# LED_Matrix16x16.net
KiCad netlist of a schematic drawn in Altium Designer
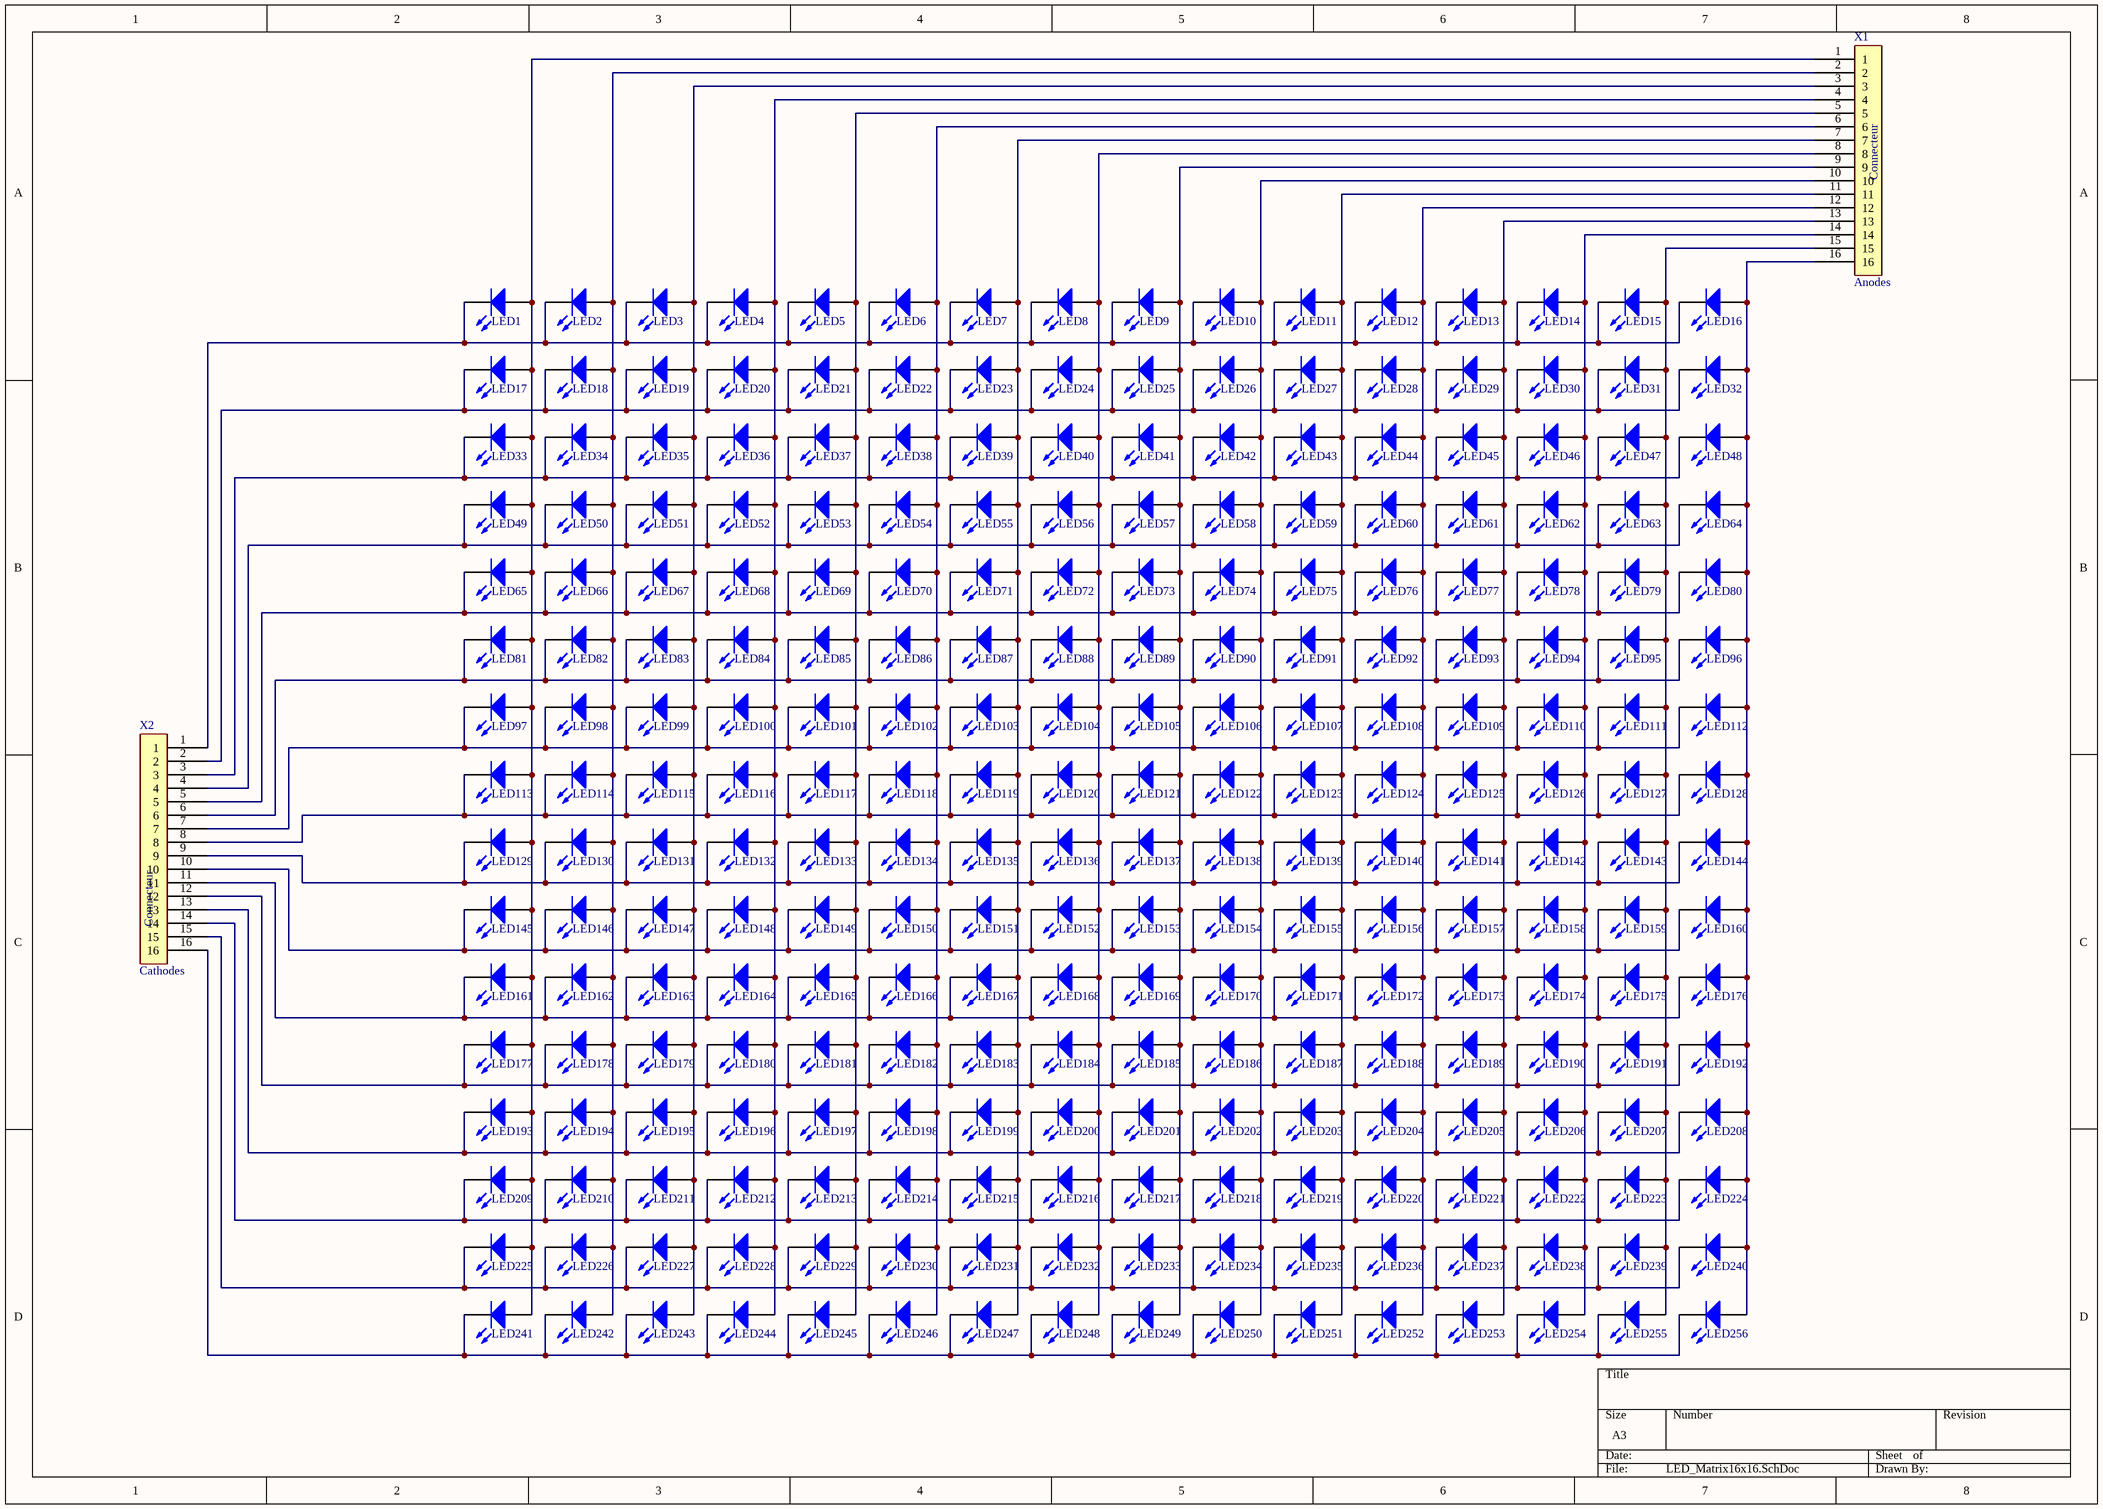
[diagram p0: LED_Matrix16x16.SchDoc]

(export (version "E")
  (design (tool "Eeschema 10.0.6"))
  (components
    (comp (ref "LED1")
      (value "KPT-2012SRC-PRV")
      (footprint "0805_LED")
      (libsource (lib "2008_SablierElectronique_SCHLIB") (part "KPT-2012SRC-PRV"))
    )
    (comp (ref "LED2")
      (value "KPT-2012SRC-PRV")
      (footprint "0805_LED")
      (libsource (lib "2008_SablierElectronique_SCHLIB") (part "KPT-2012SRC-PRV"))
    )
    (comp (ref "LED3")
      (value "KPT-2012SRC-PRV")
      (footprint "0805_LED")
      (libsource (lib "2008_SablierElectronique_SCHLIB") (part "KPT-2012SRC-PRV"))
    )
    (comp (ref "LED4")
      (value "KPT-2012SRC-PRV")
      (footprint "0805_LED")
      (libsource (lib "2008_SablierElectronique_SCHLIB") (part "KPT-2012SRC-PRV"))
    )
    (comp (ref "LED5")
      (value "KPT-2012SRC-PRV")
      (footprint "0805_LED")
      (libsource (lib "2008_SablierElectronique_SCHLIB") (part "KPT-2012SRC-PRV"))
    )
    (comp (ref "LED6")
      (value "KPT-2012SRC-PRV")
      (footprint "0805_LED")
      (libsource (lib "2008_SablierElectronique_SCHLIB") (part "KPT-2012SRC-PRV"))
    )
    (comp (ref "LED7")
      (value "KPT-2012SRC-PRV")
      (footprint "0805_LED")
      (libsource (lib "2008_SablierElectronique_SCHLIB") (part "KPT-2012SRC-PRV"))
    )
    (comp (ref "LED8")
      (value "KPT-2012SRC-PRV")
      (footprint "0805_LED")
      (libsource (lib "2008_SablierElectronique_SCHLIB") (part "KPT-2012SRC-PRV"))
    )
    (comp (ref "LED9")
      (value "KPT-2012SRC-PRV")
      (footprint "0805_LED")
      (libsource (lib "2008_SablierElectronique_SCHLIB") (part "KPT-2012SRC-PRV"))
    )
    (comp (ref "LED10")
      (value "KPT-2012SRC-PRV")
      (footprint "0805_LED")
      (libsource (lib "2008_SablierElectronique_SCHLIB") (part "KPT-2012SRC-PRV"))
    )
    (comp (ref "LED11")
      (value "KPT-2012SRC-PRV")
      (footprint "0805_LED")
      (libsource (lib "2008_SablierElectronique_SCHLIB") (part "KPT-2012SRC-PRV"))
    )
    (comp (ref "LED12")
      (value "KPT-2012SRC-PRV")
      (footprint "0805_LED")
      (libsource (lib "2008_SablierElectronique_SCHLIB") (part "KPT-2012SRC-PRV"))
    )
    (comp (ref "LED13")
      (value "KPT-2012SRC-PRV")
      (footprint "0805_LED")
      (libsource (lib "2008_SablierElectronique_SCHLIB") (part "KPT-2012SRC-PRV"))
    )
    (comp (ref "LED14")
      (value "KPT-2012SRC-PRV")
      (footprint "0805_LED")
      (libsource (lib "2008_SablierElectronique_SCHLIB") (part "KPT-2012SRC-PRV"))
    )
    (comp (ref "LED15")
      (value "KPT-2012SRC-PRV")
      (footprint "0805_LED")
      (libsource (lib "2008_SablierElectronique_SCHLIB") (part "KPT-2012SRC-PRV"))
    )
    (comp (ref "LED16")
      (value "KPT-2012SRC-PRV")
      (footprint "0805_LED")
      (libsource (lib "2008_SablierElectronique_SCHLIB") (part "KPT-2012SRC-PRV"))
    )
    (comp (ref "LED17")
      (value "KPT-2012SRC-PRV")
      (footprint "0805_LED")
      (libsource (lib "2008_SablierElectronique_SCHLIB") (part "KPT-2012SRC-PRV"))
    )
    (comp (ref "LED18")
      (value "KPT-2012SRC-PRV")
      (footprint "0805_LED")
      (libsource (lib "2008_SablierElectronique_SCHLIB") (part "KPT-2012SRC-PRV"))
    )
    (comp (ref "LED19")
      (value "KPT-2012SRC-PRV")
      (footprint "0805_LED")
      (libsource (lib "2008_SablierElectronique_SCHLIB") (part "KPT-2012SRC-PRV"))
    )
    (comp (ref "LED20")
      (value "KPT-2012SRC-PRV")
      (footprint "0805_LED")
      (libsource (lib "2008_SablierElectronique_SCHLIB") (part "KPT-2012SRC-PRV"))
    )
    (comp (ref "LED21")
      (value "KPT-2012SRC-PRV")
      (footprint "0805_LED")
      (libsource (lib "2008_SablierElectronique_SCHLIB") (part "KPT-2012SRC-PRV"))
    )
    (comp (ref "LED22")
      (value "KPT-2012SRC-PRV")
      (footprint "0805_LED")
      (libsource (lib "2008_SablierElectronique_SCHLIB") (part "KPT-2012SRC-PRV"))
    )
    (comp (ref "LED23")
      (value "KPT-2012SRC-PRV")
      (footprint "0805_LED")
      (libsource (lib "2008_SablierElectronique_SCHLIB") (part "KPT-2012SRC-PRV"))
    )
    (comp (ref "LED24")
      (value "KPT-2012SRC-PRV")
      (footprint "0805_LED")
      (libsource (lib "2008_SablierElectronique_SCHLIB") (part "KPT-2012SRC-PRV"))
    )
    (comp (ref "LED25")
      (value "KPT-2012SRC-PRV")
      (footprint "0805_LED")
      (libsource (lib "2008_SablierElectronique_SCHLIB") (part "KPT-2012SRC-PRV"))
    )
    (comp (ref "LED26")
      (value "KPT-2012SRC-PRV")
      (footprint "0805_LED")
      (libsource (lib "2008_SablierElectronique_SCHLIB") (part "KPT-2012SRC-PRV"))
    )
    (comp (ref "LED27")
      (value "KPT-2012SRC-PRV")
      (footprint "0805_LED")
      (libsource (lib "2008_SablierElectronique_SCHLIB") (part "KPT-2012SRC-PRV"))
    )
    (comp (ref "LED28")
      (value "KPT-2012SRC-PRV")
      (footprint "0805_LED")
      (libsource (lib "2008_SablierElectronique_SCHLIB") (part "KPT-2012SRC-PRV"))
    )
    (comp (ref "LED29")
      (value "KPT-2012SRC-PRV")
      (footprint "0805_LED")
      (libsource (lib "2008_SablierElectronique_SCHLIB") (part "KPT-2012SRC-PRV"))
    )
    (comp (ref "LED30")
      (value "KPT-2012SRC-PRV")
      (footprint "0805_LED")
      (libsource (lib "2008_SablierElectronique_SCHLIB") (part "KPT-2012SRC-PRV"))
    )
    (comp (ref "LED31")
      (value "KPT-2012SRC-PRV")
      (footprint "0805_LED")
      (libsource (lib "2008_SablierElectronique_SCHLIB") (part "KPT-2012SRC-PRV"))
    )
    (comp (ref "LED32")
      (value "KPT-2012SRC-PRV")
      (footprint "0805_LED")
      (libsource (lib "2008_SablierElectronique_SCHLIB") (part "KPT-2012SRC-PRV"))
    )
    (comp (ref "LED33")
      (value "KPT-2012SRC-PRV")
      (footprint "0805_LED")
      (libsource (lib "2008_SablierElectronique_SCHLIB") (part "KPT-2012SRC-PRV"))
    )
    (comp (ref "LED34")
      (value "KPT-2012SRC-PRV")
      (footprint "0805_LED")
      (libsource (lib "2008_SablierElectronique_SCHLIB") (part "KPT-2012SRC-PRV"))
    )
    (comp (ref "LED35")
      (value "KPT-2012SRC-PRV")
      (footprint "0805_LED")
      (libsource (lib "2008_SablierElectronique_SCHLIB") (part "KPT-2012SRC-PRV"))
    )
    (comp (ref "LED36")
      (value "KPT-2012SRC-PRV")
      (footprint "0805_LED")
      (libsource (lib "2008_SablierElectronique_SCHLIB") (part "KPT-2012SRC-PRV"))
    )
    (comp (ref "LED37")
      (value "KPT-2012SRC-PRV")
      (footprint "0805_LED")
      (libsource (lib "2008_SablierElectronique_SCHLIB") (part "KPT-2012SRC-PRV"))
    )
    (comp (ref "LED38")
      (value "KPT-2012SRC-PRV")
      (footprint "0805_LED")
      (libsource (lib "2008_SablierElectronique_SCHLIB") (part "KPT-2012SRC-PRV"))
    )
    (comp (ref "LED39")
      (value "KPT-2012SRC-PRV")
      (footprint "0805_LED")
      (libsource (lib "2008_SablierElectronique_SCHLIB") (part "KPT-2012SRC-PRV"))
    )
    (comp (ref "LED40")
      (value "KPT-2012SRC-PRV")
      (footprint "0805_LED")
      (libsource (lib "2008_SablierElectronique_SCHLIB") (part "KPT-2012SRC-PRV"))
    )
    (comp (ref "LED41")
      (value "KPT-2012SRC-PRV")
      (footprint "0805_LED")
      (libsource (lib "2008_SablierElectronique_SCHLIB") (part "KPT-2012SRC-PRV"))
    )
    (comp (ref "LED42")
      (value "KPT-2012SRC-PRV")
      (footprint "0805_LED")
      (libsource (lib "2008_SablierElectronique_SCHLIB") (part "KPT-2012SRC-PRV"))
    )
    (comp (ref "LED43")
      (value "KPT-2012SRC-PRV")
      (footprint "0805_LED")
      (libsource (lib "2008_SablierElectronique_SCHLIB") (part "KPT-2012SRC-PRV"))
    )
    (comp (ref "LED44")
      (value "KPT-2012SRC-PRV")
      (footprint "0805_LED")
      (libsource (lib "2008_SablierElectronique_SCHLIB") (part "KPT-2012SRC-PRV"))
    )
    (comp (ref "LED45")
      (value "KPT-2012SRC-PRV")
      (footprint "0805_LED")
      (libsource (lib "2008_SablierElectronique_SCHLIB") (part "KPT-2012SRC-PRV"))
    )
    (comp (ref "LED46")
      (value "KPT-2012SRC-PRV")
      (footprint "0805_LED")
      (libsource (lib "2008_SablierElectronique_SCHLIB") (part "KPT-2012SRC-PRV"))
    )
    (comp (ref "LED47")
      (value "KPT-2012SRC-PRV")
      (footprint "0805_LED")
      (libsource (lib "2008_SablierElectronique_SCHLIB") (part "KPT-2012SRC-PRV"))
    )
    (comp (ref "LED48")
      (value "KPT-2012SRC-PRV")
      (footprint "0805_LED")
      (libsource (lib "2008_SablierElectronique_SCHLIB") (part "KPT-2012SRC-PRV"))
    )
    (comp (ref "LED49")
      (value "KPT-2012SRC-PRV")
      (footprint "0805_LED")
      (libsource (lib "2008_SablierElectronique_SCHLIB") (part "KPT-2012SRC-PRV"))
    )
    (comp (ref "LED50")
      (value "KPT-2012SRC-PRV")
      (footprint "0805_LED")
      (libsource (lib "2008_SablierElectronique_SCHLIB") (part "KPT-2012SRC-PRV"))
    )
    (comp (ref "LED51")
      (value "KPT-2012SRC-PRV")
      (footprint "0805_LED")
      (libsource (lib "2008_SablierElectronique_SCHLIB") (part "KPT-2012SRC-PRV"))
    )
    (comp (ref "LED52")
      (value "KPT-2012SRC-PRV")
      (footprint "0805_LED")
      (libsource (lib "2008_SablierElectronique_SCHLIB") (part "KPT-2012SRC-PRV"))
    )
    (comp (ref "LED53")
      (value "KPT-2012SRC-PRV")
      (footprint "0805_LED")
      (libsource (lib "2008_SablierElectronique_SCHLIB") (part "KPT-2012SRC-PRV"))
    )
    (comp (ref "LED54")
      (value "KPT-2012SRC-PRV")
      (footprint "0805_LED")
      (libsource (lib "2008_SablierElectronique_SCHLIB") (part "KPT-2012SRC-PRV"))
    )
    (comp (ref "LED55")
      (value "KPT-2012SRC-PRV")
      (footprint "0805_LED")
      (libsource (lib "2008_SablierElectronique_SCHLIB") (part "KPT-2012SRC-PRV"))
    )
    (comp (ref "LED56")
      (value "KPT-2012SRC-PRV")
      (footprint "0805_LED")
      (libsource (lib "2008_SablierElectronique_SCHLIB") (part "KPT-2012SRC-PRV"))
    )
    (comp (ref "LED57")
      (value "KPT-2012SRC-PRV")
      (footprint "0805_LED")
      (libsource (lib "2008_SablierElectronique_SCHLIB") (part "KPT-2012SRC-PRV"))
    )
    (comp (ref "LED58")
      (value "KPT-2012SRC-PRV")
      (footprint "0805_LED")
      (libsource (lib "2008_SablierElectronique_SCHLIB") (part "KPT-2012SRC-PRV"))
    )
    (comp (ref "LED59")
      (value "KPT-2012SRC-PRV")
      (footprint "0805_LED")
      (libsource (lib "2008_SablierElectronique_SCHLIB") (part "KPT-2012SRC-PRV"))
    )
    (comp (ref "LED60")
      (value "KPT-2012SRC-PRV")
      (footprint "0805_LED")
      (libsource (lib "2008_SablierElectronique_SCHLIB") (part "KPT-2012SRC-PRV"))
    )
    (comp (ref "LED61")
      (value "KPT-2012SRC-PRV")
      (footprint "0805_LED")
      (libsource (lib "2008_SablierElectronique_SCHLIB") (part "KPT-2012SRC-PRV"))
    )
    (comp (ref "LED62")
      (value "KPT-2012SRC-PRV")
      (footprint "0805_LED")
      (libsource (lib "2008_SablierElectronique_SCHLIB") (part "KPT-2012SRC-PRV"))
    )
    (comp (ref "LED63")
      (value "KPT-2012SRC-PRV")
      (footprint "0805_LED")
      (libsource (lib "2008_SablierElectronique_SCHLIB") (part "KPT-2012SRC-PRV"))
    )
    (comp (ref "LED64")
      (value "KPT-2012SRC-PRV")
      (footprint "0805_LED")
      (libsource (lib "2008_SablierElectronique_SCHLIB") (part "KPT-2012SRC-PRV"))
    )
    (comp (ref "LED65")
      (value "KPT-2012SRC-PRV")
      (footprint "0805_LED")
      (libsource (lib "2008_SablierElectronique_SCHLIB") (part "KPT-2012SRC-PRV"))
    )
    (comp (ref "LED66")
      (value "KPT-2012SRC-PRV")
      (footprint "0805_LED")
      (libsource (lib "2008_SablierElectronique_SCHLIB") (part "KPT-2012SRC-PRV"))
    )
    (comp (ref "LED67")
      (value "KPT-2012SRC-PRV")
      (footprint "0805_LED")
      (libsource (lib "2008_SablierElectronique_SCHLIB") (part "KPT-2012SRC-PRV"))
    )
    (comp (ref "LED68")
      (value "KPT-2012SRC-PRV")
      (footprint "0805_LED")
      (libsource (lib "2008_SablierElectronique_SCHLIB") (part "KPT-2012SRC-PRV"))
    )
    (comp (ref "LED69")
      (value "KPT-2012SRC-PRV")
      (footprint "0805_LED")
      (libsource (lib "2008_SablierElectronique_SCHLIB") (part "KPT-2012SRC-PRV"))
    )
    (comp (ref "LED70")
      (value "KPT-2012SRC-PRV")
      (footprint "0805_LED")
      (libsource (lib "2008_SablierElectronique_SCHLIB") (part "KPT-2012SRC-PRV"))
    )
    (comp (ref "LED71")
      (value "KPT-2012SRC-PRV")
      (footprint "0805_LED")
      (libsource (lib "2008_SablierElectronique_SCHLIB") (part "KPT-2012SRC-PRV"))
    )
    (comp (ref "LED72")
      (value "KPT-2012SRC-PRV")
      (footprint "0805_LED")
      (libsource (lib "2008_SablierElectronique_SCHLIB") (part "KPT-2012SRC-PRV"))
    )
    (comp (ref "LED73")
      (value "KPT-2012SRC-PRV")
      (footprint "0805_LED")
      (libsource (lib "2008_SablierElectronique_SCHLIB") (part "KPT-2012SRC-PRV"))
    )
    (comp (ref "LED74")
      (value "KPT-2012SRC-PRV")
      (footprint "0805_LED")
      (libsource (lib "2008_SablierElectronique_SCHLIB") (part "KPT-2012SRC-PRV"))
    )
    (comp (ref "LED75")
      (value "KPT-2012SRC-PRV")
      (footprint "0805_LED")
      (libsource (lib "2008_SablierElectronique_SCHLIB") (part "KPT-2012SRC-PRV"))
    )
    (comp (ref "LED76")
      (value "KPT-2012SRC-PRV")
      (footprint "0805_LED")
      (libsource (lib "2008_SablierElectronique_SCHLIB") (part "KPT-2012SRC-PRV"))
    )
    (comp (ref "LED77")
      (value "KPT-2012SRC-PRV")
      (footprint "0805_LED")
      (libsource (lib "2008_SablierElectronique_SCHLIB") (part "KPT-2012SRC-PRV"))
    )
    (comp (ref "LED78")
      (value "KPT-2012SRC-PRV")
      (footprint "0805_LED")
      (libsource (lib "2008_SablierElectronique_SCHLIB") (part "KPT-2012SRC-PRV"))
    )
    (comp (ref "LED79")
      (value "KPT-2012SRC-PRV")
      (footprint "0805_LED")
      (libsource (lib "2008_SablierElectronique_SCHLIB") (part "KPT-2012SRC-PRV"))
    )
    (comp (ref "LED80")
      (value "KPT-2012SRC-PRV")
      (footprint "0805_LED")
      (libsource (lib "2008_SablierElectronique_SCHLIB") (part "KPT-2012SRC-PRV"))
    )
    (comp (ref "LED81")
      (value "KPT-2012SRC-PRV")
      (footprint "0805_LED")
      (libsource (lib "2008_SablierElectronique_SCHLIB") (part "KPT-2012SRC-PRV"))
    )
    (comp (ref "LED82")
      (value "KPT-2012SRC-PRV")
      (footprint "0805_LED")
      (libsource (lib "2008_SablierElectronique_SCHLIB") (part "KPT-2012SRC-PRV"))
    )
    (comp (ref "LED83")
      (value "KPT-2012SRC-PRV")
      (footprint "0805_LED")
      (libsource (lib "2008_SablierElectronique_SCHLIB") (part "KPT-2012SRC-PRV"))
    )
    (comp (ref "LED84")
      (value "KPT-2012SRC-PRV")
      (footprint "0805_LED")
      (libsource (lib "2008_SablierElectronique_SCHLIB") (part "KPT-2012SRC-PRV"))
    )
    (comp (ref "LED85")
      (value "KPT-2012SRC-PRV")
      (footprint "0805_LED")
      (libsource (lib "2008_SablierElectronique_SCHLIB") (part "KPT-2012SRC-PRV"))
    )
    (comp (ref "LED86")
      (value "KPT-2012SRC-PRV")
      (footprint "0805_LED")
      (libsource (lib "2008_SablierElectronique_SCHLIB") (part "KPT-2012SRC-PRV"))
    )
    (comp (ref "LED87")
      (value "KPT-2012SRC-PRV")
      (footprint "0805_LED")
      (libsource (lib "2008_SablierElectronique_SCHLIB") (part "KPT-2012SRC-PRV"))
    )
    (comp (ref "LED88")
      (value "KPT-2012SRC-PRV")
      (footprint "0805_LED")
      (libsource (lib "2008_SablierElectronique_SCHLIB") (part "KPT-2012SRC-PRV"))
    )
    (comp (ref "LED89")
      (value "KPT-2012SRC-PRV")
      (footprint "0805_LED")
      (libsource (lib "2008_SablierElectronique_SCHLIB") (part "KPT-2012SRC-PRV"))
    )
    (comp (ref "LED90")
      (value "KPT-2012SRC-PRV")
      (footprint "0805_LED")
      (libsource (lib "2008_SablierElectronique_SCHLIB") (part "KPT-2012SRC-PRV"))
    )
    (comp (ref "LED91")
      (value "KPT-2012SRC-PRV")
      (footprint "0805_LED")
      (libsource (lib "2008_SablierElectronique_SCHLIB") (part "KPT-2012SRC-PRV"))
    )
    (comp (ref "LED92")
      (value "KPT-2012SRC-PRV")
      (footprint "0805_LED")
      (libsource (lib "2008_SablierElectronique_SCHLIB") (part "KPT-2012SRC-PRV"))
    )
    (comp (ref "LED93")
      (value "KPT-2012SRC-PRV")
      (footprint "0805_LED")
      (libsource (lib "2008_SablierElectronique_SCHLIB") (part "KPT-2012SRC-PRV"))
    )
    (comp (ref "LED94")
      (value "KPT-2012SRC-PRV")
      (footprint "0805_LED")
      (libsource (lib "2008_SablierElectronique_SCHLIB") (part "KPT-2012SRC-PRV"))
    )
    (comp (ref "LED95")
      (value "KPT-2012SRC-PRV")
      (footprint "0805_LED")
      (libsource (lib "2008_SablierElectronique_SCHLIB") (part "KPT-2012SRC-PRV"))
    )
    (comp (ref "LED96")
      (value "KPT-2012SRC-PRV")
      (footprint "0805_LED")
      (libsource (lib "2008_SablierElectronique_SCHLIB") (part "KPT-2012SRC-PRV"))
    )
    (comp (ref "LED97")
      (value "KPT-2012SRC-PRV")
      (footprint "0805_LED")
      (libsource (lib "2008_SablierElectronique_SCHLIB") (part "KPT-2012SRC-PRV"))
    )
    (comp (ref "LED98")
      (value "KPT-2012SRC-PRV")
      (footprint "0805_LED")
      (libsource (lib "2008_SablierElectronique_SCHLIB") (part "KPT-2012SRC-PRV"))
    )
    (comp (ref "LED99")
      (value "KPT-2012SRC-PRV")
      (footprint "0805_LED")
      (libsource (lib "2008_SablierElectronique_SCHLIB") (part "KPT-2012SRC-PRV"))
    )
    (comp (ref "LED100")
      (value "KPT-2012SRC-PRV")
      (footprint "0805_LED")
      (libsource (lib "2008_SablierElectronique_SCHLIB") (part "KPT-2012SRC-PRV"))
    )
    (comp (ref "LED101")
      (value "KPT-2012SRC-PRV")
      (footprint "0805_LED")
      (libsource (lib "2008_SablierElectronique_SCHLIB") (part "KPT-2012SRC-PRV"))
    )
    (comp (ref "LED102")
      (value "KPT-2012SRC-PRV")
      (footprint "0805_LED")
      (libsource (lib "2008_SablierElectronique_SCHLIB") (part "KPT-2012SRC-PRV"))
    )
    (comp (ref "LED103")
      (value "KPT-2012SRC-PRV")
      (footprint "0805_LED")
      (libsource (lib "2008_SablierElectronique_SCHLIB") (part "KPT-2012SRC-PRV"))
    )
    (comp (ref "LED104")
      (value "KPT-2012SRC-PRV")
      (footprint "0805_LED")
      (libsource (lib "2008_SablierElectronique_SCHLIB") (part "KPT-2012SRC-PRV"))
    )
    (comp (ref "LED105")
      (value "KPT-2012SRC-PRV")
      (footprint "0805_LED")
      (libsource (lib "2008_SablierElectronique_SCHLIB") (part "KPT-2012SRC-PRV"))
    )
    (comp (ref "LED106")
      (value "KPT-2012SRC-PRV")
      (footprint "0805_LED")
      (libsource (lib "2008_SablierElectronique_SCHLIB") (part "KPT-2012SRC-PRV"))
    )
    (comp (ref "LED107")
      (value "KPT-2012SRC-PRV")
      (footprint "0805_LED")
      (libsource (lib "2008_SablierElectronique_SCHLIB") (part "KPT-2012SRC-PRV"))
    )
    (comp (ref "LED108")
      (value "KPT-2012SRC-PRV")
      (footprint "0805_LED")
      (libsource (lib "2008_SablierElectronique_SCHLIB") (part "KPT-2012SRC-PRV"))
    )
    (comp (ref "LED109")
      (value "KPT-2012SRC-PRV")
      (footprint "0805_LED")
      (libsource (lib "2008_SablierElectronique_SCHLIB") (part "KPT-2012SRC-PRV"))
    )
    (comp (ref "LED110")
      (value "KPT-2012SRC-PRV")
      (footprint "0805_LED")
      (libsource (lib "2008_SablierElectronique_SCHLIB") (part "KPT-2012SRC-PRV"))
    )
    (comp (ref "LED111")
      (value "KPT-2012SRC-PRV")
      (footprint "0805_LED")
      (libsource (lib "2008_SablierElectronique_SCHLIB") (part "KPT-2012SRC-PRV"))
    )
    (comp (ref "LED112")
      (value "KPT-2012SRC-PRV")
      (footprint "0805_LED")
      (libsource (lib "2008_SablierElectronique_SCHLIB") (part "KPT-2012SRC-PRV"))
    )
    (comp (ref "LED113")
      (value "KPT-2012SRC-PRV")
      (footprint "0805_LED")
      (libsource (lib "2008_SablierElectronique_SCHLIB") (part "KPT-2012SRC-PRV"))
    )
    (comp (ref "LED114")
      (value "KPT-2012SRC-PRV")
      (footprint "0805_LED")
      (libsource (lib "2008_SablierElectronique_SCHLIB") (part "KPT-2012SRC-PRV"))
    )
    (comp (ref "LED115")
      (value "KPT-2012SRC-PRV")
      (footprint "0805_LED")
      (libsource (lib "2008_SablierElectronique_SCHLIB") (part "KPT-2012SRC-PRV"))
    )
    (comp (ref "LED116")
      (value "KPT-2012SRC-PRV")
      (footprint "0805_LED")
      (libsource (lib "2008_SablierElectronique_SCHLIB") (part "KPT-2012SRC-PRV"))
    )
    (comp (ref "LED117")
      (value "KPT-2012SRC-PRV")
      (footprint "0805_LED")
      (libsource (lib "2008_SablierElectronique_SCHLIB") (part "KPT-2012SRC-PRV"))
    )
    (comp (ref "LED118")
      (value "KPT-2012SRC-PRV")
      (footprint "0805_LED")
      (libsource (lib "2008_SablierElectronique_SCHLIB") (part "KPT-2012SRC-PRV"))
    )
    (comp (ref "LED119")
      (value "KPT-2012SRC-PRV")
      (footprint "0805_LED")
      (libsource (lib "2008_SablierElectronique_SCHLIB") (part "KPT-2012SRC-PRV"))
    )
    (comp (ref "LED120")
      (value "KPT-2012SRC-PRV")
      (footprint "0805_LED")
      (libsource (lib "2008_SablierElectronique_SCHLIB") (part "KPT-2012SRC-PRV"))
    )
    (comp (ref "LED121")
      (value "KPT-2012SRC-PRV")
      (footprint "0805_LED")
      (libsource (lib "2008_SablierElectronique_SCHLIB") (part "KPT-2012SRC-PRV"))
    )
    (comp (ref "LED122")
      (value "KPT-2012SRC-PRV")
      (footprint "0805_LED")
      (libsource (lib "2008_SablierElectronique_SCHLIB") (part "KPT-2012SRC-PRV"))
    )
    (comp (ref "LED123")
      (value "KPT-2012SRC-PRV")
      (footprint "0805_LED")
      (libsource (lib "2008_SablierElectronique_SCHLIB") (part "KPT-2012SRC-PRV"))
    )
    (comp (ref "LED124")
      (value "KPT-2012SRC-PRV")
      (footprint "0805_LED")
      (libsource (lib "2008_SablierElectronique_SCHLIB") (part "KPT-2012SRC-PRV"))
    )
    (comp (ref "LED125")
      (value "KPT-2012SRC-PRV")
      (footprint "0805_LED")
      (libsource (lib "2008_SablierElectronique_SCHLIB") (part "KPT-2012SRC-PRV"))
    )
    (comp (ref "LED126")
      (value "KPT-2012SRC-PRV")
      (footprint "0805_LED")
      (libsource (lib "2008_SablierElectronique_SCHLIB") (part "KPT-2012SRC-PRV"))
    )
    (comp (ref "LED127")
      (value "KPT-2012SRC-PRV")
      (footprint "0805_LED")
      (libsource (lib "2008_SablierElectronique_SCHLIB") (part "KPT-2012SRC-PRV"))
    )
    (comp (ref "LED128")
      (value "KPT-2012SRC-PRV")
      (footprint "0805_LED")
      (libsource (lib "2008_SablierElectronique_SCHLIB") (part "KPT-2012SRC-PRV"))
    )
    (comp (ref "LED129")
      (value "KPT-2012SRC-PRV")
      (footprint "0805_LED")
      (libsource (lib "2008_SablierElectronique_SCHLIB") (part "KPT-2012SRC-PRV"))
    )
    (comp (ref "LED130")
      (value "KPT-2012SRC-PRV")
      (footprint "0805_LED")
      (libsource (lib "2008_SablierElectronique_SCHLIB") (part "KPT-2012SRC-PRV"))
    )
    (comp (ref "LED131")
      (value "KPT-2012SRC-PRV")
      (footprint "0805_LED")
      (libsource (lib "2008_SablierElectronique_SCHLIB") (part "KPT-2012SRC-PRV"))
    )
    (comp (ref "LED132")
      (value "KPT-2012SRC-PRV")
      (footprint "0805_LED")
      (libsource (lib "2008_SablierElectronique_SCHLIB") (part "KPT-2012SRC-PRV"))
    )
    (comp (ref "LED133")
      (value "KPT-2012SRC-PRV")
      (footprint "0805_LED")
      (libsource (lib "2008_SablierElectronique_SCHLIB") (part "KPT-2012SRC-PRV"))
    )
    (comp (ref "LED134")
      (value "KPT-2012SRC-PRV")
      (footprint "0805_LED")
      (libsource (lib "2008_SablierElectronique_SCHLIB") (part "KPT-2012SRC-PRV"))
    )
    (comp (ref "LED135")
      (value "KPT-2012SRC-PRV")
      (footprint "0805_LED")
      (libsource (lib "2008_SablierElectronique_SCHLIB") (part "KPT-2012SRC-PRV"))
    )
    (comp (ref "LED136")
      (value "KPT-2012SRC-PRV")
      (footprint "0805_LED")
      (libsource (lib "2008_SablierElectronique_SCHLIB") (part "KPT-2012SRC-PRV"))
    )
    (comp (ref "LED137")
      (value "KPT-2012SRC-PRV")
      (footprint "0805_LED")
      (libsource (lib "2008_SablierElectronique_SCHLIB") (part "KPT-2012SRC-PRV"))
    )
    (comp (ref "LED138")
      (value "KPT-2012SRC-PRV")
      (footprint "0805_LED")
      (libsource (lib "2008_SablierElectronique_SCHLIB") (part "KPT-2012SRC-PRV"))
    )
    (comp (ref "LED139")
      (value "KPT-2012SRC-PRV")
      (footprint "0805_LED")
      (libsource (lib "2008_SablierElectronique_SCHLIB") (part "KPT-2012SRC-PRV"))
    )
    (comp (ref "LED140")
      (value "KPT-2012SRC-PRV")
      (footprint "0805_LED")
      (libsource (lib "2008_SablierElectronique_SCHLIB") (part "KPT-2012SRC-PRV"))
    )
    (comp (ref "LED141")
      (value "KPT-2012SRC-PRV")
      (footprint "0805_LED")
      (libsource (lib "2008_SablierElectronique_SCHLIB") (part "KPT-2012SRC-PRV"))
    )
    (comp (ref "LED142")
      (value "KPT-2012SRC-PRV")
      (footprint "0805_LED")
      (libsource (lib "2008_SablierElectronique_SCHLIB") (part "KPT-2012SRC-PRV"))
    )
    (comp (ref "LED143")
      (value "KPT-2012SRC-PRV")
      (footprint "0805_LED")
      (libsource (lib "2008_SablierElectronique_SCHLIB") (part "KPT-2012SRC-PRV"))
    )
    (comp (ref "LED144")
      (value "KPT-2012SRC-PRV")
      (footprint "0805_LED")
      (libsource (lib "2008_SablierElectronique_SCHLIB") (part "KPT-2012SRC-PRV"))
    )
    (comp (ref "LED145")
      (value "KPT-2012SRC-PRV")
      (footprint "0805_LED")
      (libsource (lib "2008_SablierElectronique_SCHLIB") (part "KPT-2012SRC-PRV"))
    )
    (comp (ref "LED146")
      (value "KPT-2012SRC-PRV")
      (footprint "0805_LED")
      (libsource (lib "2008_SablierElectronique_SCHLIB") (part "KPT-2012SRC-PRV"))
    )
    (comp (ref "LED147")
      (value "KPT-2012SRC-PRV")
      (footprint "0805_LED")
      (libsource (lib "2008_SablierElectronique_SCHLIB") (part "KPT-2012SRC-PRV"))
    )
    (comp (ref "LED148")
      (value "KPT-2012SRC-PRV")
      (footprint "0805_LED")
      (libsource (lib "2008_SablierElectronique_SCHLIB") (part "KPT-2012SRC-PRV"))
    )
    (comp (ref "LED149")
      (value "KPT-2012SRC-PRV")
      (footprint "0805_LED")
      (libsource (lib "2008_SablierElectronique_SCHLIB") (part "KPT-2012SRC-PRV"))
    )
    (comp (ref "LED150")
      (value "KPT-2012SRC-PRV")
      (footprint "0805_LED")
      (libsource (lib "2008_SablierElectronique_SCHLIB") (part "KPT-2012SRC-PRV"))
    )
    (comp (ref "LED151")
      (value "KPT-2012SRC-PRV")
      (footprint "0805_LED")
      (libsource (lib "2008_SablierElectronique_SCHLIB") (part "KPT-2012SRC-PRV"))
    )
    (comp (ref "LED152")
      (value "KPT-2012SRC-PRV")
      (footprint "0805_LED")
      (libsource (lib "2008_SablierElectronique_SCHLIB") (part "KPT-2012SRC-PRV"))
    )
    (comp (ref "LED153")
      (value "KPT-2012SRC-PRV")
      (footprint "0805_LED")
      (libsource (lib "2008_SablierElectronique_SCHLIB") (part "KPT-2012SRC-PRV"))
    )
    (comp (ref "LED154")
      (value "KPT-2012SRC-PRV")
      (footprint "0805_LED")
      (libsource (lib "2008_SablierElectronique_SCHLIB") (part "KPT-2012SRC-PRV"))
    )
    (comp (ref "LED155")
      (value "KPT-2012SRC-PRV")
      (footprint "0805_LED")
      (libsource (lib "2008_SablierElectronique_SCHLIB") (part "KPT-2012SRC-PRV"))
    )
    (comp (ref "LED156")
      (value "KPT-2012SRC-PRV")
      (footprint "0805_LED")
      (libsource (lib "2008_SablierElectronique_SCHLIB") (part "KPT-2012SRC-PRV"))
    )
    (comp (ref "LED157")
      (value "KPT-2012SRC-PRV")
      (footprint "0805_LED")
      (libsource (lib "2008_SablierElectronique_SCHLIB") (part "KPT-2012SRC-PRV"))
    )
    (comp (ref "LED158")
      (value "KPT-2012SRC-PRV")
      (footprint "0805_LED")
      (libsource (lib "2008_SablierElectronique_SCHLIB") (part "KPT-2012SRC-PRV"))
    )
    (comp (ref "LED159")
      (value "KPT-2012SRC-PRV")
      (footprint "0805_LED")
      (libsource (lib "2008_SablierElectronique_SCHLIB") (part "KPT-2012SRC-PRV"))
    )
    (comp (ref "LED160")
      (value "KPT-2012SRC-PRV")
      (footprint "0805_LED")
      (libsource (lib "2008_SablierElectronique_SCHLIB") (part "KPT-2012SRC-PRV"))
    )
    (comp (ref "LED161")
      (value "KPT-2012SRC-PRV")
      (footprint "0805_LED")
      (libsource (lib "2008_SablierElectronique_SCHLIB") (part "KPT-2012SRC-PRV"))
    )
    (comp (ref "LED162")
      (value "KPT-2012SRC-PRV")
      (footprint "0805_LED")
      (libsource (lib "2008_SablierElectronique_SCHLIB") (part "KPT-2012SRC-PRV"))
    )
    (comp (ref "LED163")
      (value "KPT-2012SRC-PRV")
      (footprint "0805_LED")
      (libsource (lib "2008_SablierElectronique_SCHLIB") (part "KPT-2012SRC-PRV"))
    )
    (comp (ref "LED164")
      (value "KPT-2012SRC-PRV")
      (footprint "0805_LED")
      (libsource (lib "2008_SablierElectronique_SCHLIB") (part "KPT-2012SRC-PRV"))
    )
    (comp (ref "LED165")
      (value "KPT-2012SRC-PRV")
      (footprint "0805_LED")
      (libsource (lib "2008_SablierElectronique_SCHLIB") (part "KPT-2012SRC-PRV"))
    )
    (comp (ref "LED166")
      (value "KPT-2012SRC-PRV")
      (footprint "0805_LED")
      (libsource (lib "2008_SablierElectronique_SCHLIB") (part "KPT-2012SRC-PRV"))
    )
    (comp (ref "LED167")
      (value "KPT-2012SRC-PRV")
      (footprint "0805_LED")
      (libsource (lib "2008_SablierElectronique_SCHLIB") (part "KPT-2012SRC-PRV"))
    )
    (comp (ref "LED168")
      (value "KPT-2012SRC-PRV")
      (footprint "0805_LED")
      (libsource (lib "2008_SablierElectronique_SCHLIB") (part "KPT-2012SRC-PRV"))
    )
    (comp (ref "LED169")
      (value "KPT-2012SRC-PRV")
      (footprint "0805_LED")
      (libsource (lib "2008_SablierElectronique_SCHLIB") (part "KPT-2012SRC-PRV"))
    )
    (comp (ref "LED170")
      (value "KPT-2012SRC-PRV")
      (footprint "0805_LED")
      (libsource (lib "2008_SablierElectronique_SCHLIB") (part "KPT-2012SRC-PRV"))
    )
    (comp (ref "LED171")
      (value "KPT-2012SRC-PRV")
      (footprint "0805_LED")
      (libsource (lib "2008_SablierElectronique_SCHLIB") (part "KPT-2012SRC-PRV"))
    )
    (comp (ref "LED172")
      (value "KPT-2012SRC-PRV")
      (footprint "0805_LED")
      (libsource (lib "2008_SablierElectronique_SCHLIB") (part "KPT-2012SRC-PRV"))
    )
    (comp (ref "LED173")
      (value "KPT-2012SRC-PRV")
      (footprint "0805_LED")
      (libsource (lib "2008_SablierElectronique_SCHLIB") (part "KPT-2012SRC-PRV"))
    )
    (comp (ref "LED174")
      (value "KPT-2012SRC-PRV")
      (footprint "0805_LED")
      (libsource (lib "2008_SablierElectronique_SCHLIB") (part "KPT-2012SRC-PRV"))
    )
    (comp (ref "LED175")
      (value "KPT-2012SRC-PRV")
      (footprint "0805_LED")
      (libsource (lib "2008_SablierElectronique_SCHLIB") (part "KPT-2012SRC-PRV"))
    )
    (comp (ref "LED176")
      (value "KPT-2012SRC-PRV")
      (footprint "0805_LED")
      (libsource (lib "2008_SablierElectronique_SCHLIB") (part "KPT-2012SRC-PRV"))
    )
    (comp (ref "LED177")
      (value "KPT-2012SRC-PRV")
      (footprint "0805_LED")
      (libsource (lib "2008_SablierElectronique_SCHLIB") (part "KPT-2012SRC-PRV"))
    )
    (comp (ref "LED178")
      (value "KPT-2012SRC-PRV")
      (footprint "0805_LED")
      (libsource (lib "2008_SablierElectronique_SCHLIB") (part "KPT-2012SRC-PRV"))
    )
    (comp (ref "LED179")
      (value "KPT-2012SRC-PRV")
      (footprint "0805_LED")
      (libsource (lib "2008_SablierElectronique_SCHLIB") (part "KPT-2012SRC-PRV"))
    )
    (comp (ref "LED180")
      (value "KPT-2012SRC-PRV")
      (footprint "0805_LED")
      (libsource (lib "2008_SablierElectronique_SCHLIB") (part "KPT-2012SRC-PRV"))
    )
    (comp (ref "LED181")
      (value "KPT-2012SRC-PRV")
      (footprint "0805_LED")
      (libsource (lib "2008_SablierElectronique_SCHLIB") (part "KPT-2012SRC-PRV"))
    )
    (comp (ref "LED182")
      (value "KPT-2012SRC-PRV")
      (footprint "0805_LED")
      (libsource (lib "2008_SablierElectronique_SCHLIB") (part "KPT-2012SRC-PRV"))
    )
    (comp (ref "LED183")
      (value "KPT-2012SRC-PRV")
      (footprint "0805_LED")
      (libsource (lib "2008_SablierElectronique_SCHLIB") (part "KPT-2012SRC-PRV"))
    )
    (comp (ref "LED184")
      (value "KPT-2012SRC-PRV")
      (footprint "0805_LED")
      (libsource (lib "2008_SablierElectronique_SCHLIB") (part "KPT-2012SRC-PRV"))
    )
    (comp (ref "LED185")
      (value "KPT-2012SRC-PRV")
      (footprint "0805_LED")
      (libsource (lib "2008_SablierElectronique_SCHLIB") (part "KPT-2012SRC-PRV"))
    )
    (comp (ref "LED186")
      (value "KPT-2012SRC-PRV")
      (footprint "0805_LED")
      (libsource (lib "2008_SablierElectronique_SCHLIB") (part "KPT-2012SRC-PRV"))
    )
    (comp (ref "LED187")
      (value "KPT-2012SRC-PRV")
      (footprint "0805_LED")
      (libsource (lib "2008_SablierElectronique_SCHLIB") (part "KPT-2012SRC-PRV"))
    )
    (comp (ref "LED188")
      (value "KPT-2012SRC-PRV")
      (footprint "0805_LED")
      (libsource (lib "2008_SablierElectronique_SCHLIB") (part "KPT-2012SRC-PRV"))
    )
    (comp (ref "LED189")
      (value "KPT-2012SRC-PRV")
      (footprint "0805_LED")
      (libsource (lib "2008_SablierElectronique_SCHLIB") (part "KPT-2012SRC-PRV"))
    )
    (comp (ref "LED190")
      (value "KPT-2012SRC-PRV")
      (footprint "0805_LED")
      (libsource (lib "2008_SablierElectronique_SCHLIB") (part "KPT-2012SRC-PRV"))
    )
    (comp (ref "LED191")
      (value "KPT-2012SRC-PRV")
      (footprint "0805_LED")
      (libsource (lib "2008_SablierElectronique_SCHLIB") (part "KPT-2012SRC-PRV"))
    )
    (comp (ref "LED192")
      (value "KPT-2012SRC-PRV")
      (footprint "0805_LED")
      (libsource (lib "2008_SablierElectronique_SCHLIB") (part "KPT-2012SRC-PRV"))
    )
    (comp (ref "LED193")
      (value "KPT-2012SRC-PRV")
      (footprint "0805_LED")
      (libsource (lib "2008_SablierElectronique_SCHLIB") (part "KPT-2012SRC-PRV"))
    )
    (comp (ref "LED194")
      (value "KPT-2012SRC-PRV")
      (footprint "0805_LED")
      (libsource (lib "2008_SablierElectronique_SCHLIB") (part "KPT-2012SRC-PRV"))
    )
    (comp (ref "LED195")
      (value "KPT-2012SRC-PRV")
      (footprint "0805_LED")
      (libsource (lib "2008_SablierElectronique_SCHLIB") (part "KPT-2012SRC-PRV"))
    )
    (comp (ref "LED196")
      (value "KPT-2012SRC-PRV")
      (footprint "0805_LED")
      (libsource (lib "2008_SablierElectronique_SCHLIB") (part "KPT-2012SRC-PRV"))
    )
    (comp (ref "LED197")
      (value "KPT-2012SRC-PRV")
      (footprint "0805_LED")
      (libsource (lib "2008_SablierElectronique_SCHLIB") (part "KPT-2012SRC-PRV"))
    )
    (comp (ref "LED198")
      (value "KPT-2012SRC-PRV")
      (footprint "0805_LED")
      (libsource (lib "2008_SablierElectronique_SCHLIB") (part "KPT-2012SRC-PRV"))
    )
    (comp (ref "LED199")
      (value "KPT-2012SRC-PRV")
      (footprint "0805_LED")
      (libsource (lib "2008_SablierElectronique_SCHLIB") (part "KPT-2012SRC-PRV"))
    )
    (comp (ref "LED200")
      (value "KPT-2012SRC-PRV")
      (footprint "0805_LED")
      (libsource (lib "2008_SablierElectronique_SCHLIB") (part "KPT-2012SRC-PRV"))
    )
    (comp (ref "LED201")
      (value "KPT-2012SRC-PRV")
      (footprint "0805_LED")
      (libsource (lib "2008_SablierElectronique_SCHLIB") (part "KPT-2012SRC-PRV"))
    )
    (comp (ref "LED202")
      (value "KPT-2012SRC-PRV")
      (footprint "0805_LED")
      (libsource (lib "2008_SablierElectronique_SCHLIB") (part "KPT-2012SRC-PRV"))
    )
    (comp (ref "LED203")
      (value "KPT-2012SRC-PRV")
      (footprint "0805_LED")
      (libsource (lib "2008_SablierElectronique_SCHLIB") (part "KPT-2012SRC-PRV"))
    )
    (comp (ref "LED204")
      (value "KPT-2012SRC-PRV")
      (footprint "0805_LED")
      (libsource (lib "2008_SablierElectronique_SCHLIB") (part "KPT-2012SRC-PRV"))
    )
    (comp (ref "LED205")
      (value "KPT-2012SRC-PRV")
      (footprint "0805_LED")
      (libsource (lib "2008_SablierElectronique_SCHLIB") (part "KPT-2012SRC-PRV"))
    )
    (comp (ref "LED206")
      (value "KPT-2012SRC-PRV")
      (footprint "0805_LED")
      (libsource (lib "2008_SablierElectronique_SCHLIB") (part "KPT-2012SRC-PRV"))
    )
    (comp (ref "LED207")
      (value "KPT-2012SRC-PRV")
      (footprint "0805_LED")
      (libsource (lib "2008_SablierElectronique_SCHLIB") (part "KPT-2012SRC-PRV"))
    )
    (comp (ref "LED208")
      (value "KPT-2012SRC-PRV")
      (footprint "0805_LED")
      (libsource (lib "2008_SablierElectronique_SCHLIB") (part "KPT-2012SRC-PRV"))
    )
    (comp (ref "LED209")
      (value "KPT-2012SRC-PRV")
      (footprint "0805_LED")
      (libsource (lib "2008_SablierElectronique_SCHLIB") (part "KPT-2012SRC-PRV"))
    )
    (comp (ref "LED210")
      (value "KPT-2012SRC-PRV")
      (footprint "0805_LED")
      (libsource (lib "2008_SablierElectronique_SCHLIB") (part "KPT-2012SRC-PRV"))
    )
    (comp (ref "LED211")
      (value "KPT-2012SRC-PRV")
      (footprint "0805_LED")
      (libsource (lib "2008_SablierElectronique_SCHLIB") (part "KPT-2012SRC-PRV"))
    )
    (comp (ref "LED212")
      (value "KPT-2012SRC-PRV")
      (footprint "0805_LED")
      (libsource (lib "2008_SablierElectronique_SCHLIB") (part "KPT-2012SRC-PRV"))
    )
    (comp (ref "LED213")
      (value "KPT-2012SRC-PRV")
      (footprint "0805_LED")
      (libsource (lib "2008_SablierElectronique_SCHLIB") (part "KPT-2012SRC-PRV"))
    )
    (comp (ref "LED214")
      (value "KPT-2012SRC-PRV")
      (footprint "0805_LED")
      (libsource (lib "2008_SablierElectronique_SCHLIB") (part "KPT-2012SRC-PRV"))
    )
    (comp (ref "LED215")
      (value "KPT-2012SRC-PRV")
      (footprint "0805_LED")
      (libsource (lib "2008_SablierElectronique_SCHLIB") (part "KPT-2012SRC-PRV"))
    )
    (comp (ref "LED216")
      (value "KPT-2012SRC-PRV")
      (footprint "0805_LED")
      (libsource (lib "2008_SablierElectronique_SCHLIB") (part "KPT-2012SRC-PRV"))
    )
    (comp (ref "LED217")
      (value "KPT-2012SRC-PRV")
      (footprint "0805_LED")
      (libsource (lib "2008_SablierElectronique_SCHLIB") (part "KPT-2012SRC-PRV"))
    )
    (comp (ref "LED218")
      (value "KPT-2012SRC-PRV")
      (footprint "0805_LED")
      (libsource (lib "2008_SablierElectronique_SCHLIB") (part "KPT-2012SRC-PRV"))
    )
    (comp (ref "LED219")
      (value "KPT-2012SRC-PRV")
      (footprint "0805_LED")
      (libsource (lib "2008_SablierElectronique_SCHLIB") (part "KPT-2012SRC-PRV"))
    )
    (comp (ref "LED220")
      (value "KPT-2012SRC-PRV")
      (footprint "0805_LED")
      (libsource (lib "2008_SablierElectronique_SCHLIB") (part "KPT-2012SRC-PRV"))
    )
    (comp (ref "LED221")
      (value "KPT-2012SRC-PRV")
      (footprint "0805_LED")
      (libsource (lib "2008_SablierElectronique_SCHLIB") (part "KPT-2012SRC-PRV"))
    )
    (comp (ref "LED222")
      (value "KPT-2012SRC-PRV")
      (footprint "0805_LED")
      (libsource (lib "2008_SablierElectronique_SCHLIB") (part "KPT-2012SRC-PRV"))
    )
    (comp (ref "LED223")
      (value "KPT-2012SRC-PRV")
      (footprint "0805_LED")
      (libsource (lib "2008_SablierElectronique_SCHLIB") (part "KPT-2012SRC-PRV"))
    )
    (comp (ref "LED224")
      (value "KPT-2012SRC-PRV")
      (footprint "0805_LED")
      (libsource (lib "2008_SablierElectronique_SCHLIB") (part "KPT-2012SRC-PRV"))
    )
    (comp (ref "LED225")
      (value "KPT-2012SRC-PRV")
      (footprint "0805_LED")
      (libsource (lib "2008_SablierElectronique_SCHLIB") (part "KPT-2012SRC-PRV"))
    )
    (comp (ref "LED226")
      (value "KPT-2012SRC-PRV")
      (footprint "0805_LED")
      (libsource (lib "2008_SablierElectronique_SCHLIB") (part "KPT-2012SRC-PRV"))
    )
    (comp (ref "LED227")
      (value "KPT-2012SRC-PRV")
      (footprint "0805_LED")
      (libsource (lib "2008_SablierElectronique_SCHLIB") (part "KPT-2012SRC-PRV"))
    )
    (comp (ref "LED228")
      (value "KPT-2012SRC-PRV")
      (footprint "0805_LED")
      (libsource (lib "2008_SablierElectronique_SCHLIB") (part "KPT-2012SRC-PRV"))
    )
    (comp (ref "LED229")
      (value "KPT-2012SRC-PRV")
      (footprint "0805_LED")
      (libsource (lib "2008_SablierElectronique_SCHLIB") (part "KPT-2012SRC-PRV"))
    )
    (comp (ref "LED230")
      (value "KPT-2012SRC-PRV")
      (footprint "0805_LED")
      (libsource (lib "2008_SablierElectronique_SCHLIB") (part "KPT-2012SRC-PRV"))
    )
    (comp (ref "LED231")
      (value "KPT-2012SRC-PRV")
      (footprint "0805_LED")
      (libsource (lib "2008_SablierElectronique_SCHLIB") (part "KPT-2012SRC-PRV"))
    )
    (comp (ref "LED232")
      (value "KPT-2012SRC-PRV")
      (footprint "0805_LED")
      (libsource (lib "2008_SablierElectronique_SCHLIB") (part "KPT-2012SRC-PRV"))
    )
    (comp (ref "LED233")
      (value "KPT-2012SRC-PRV")
      (footprint "0805_LED")
      (libsource (lib "2008_SablierElectronique_SCHLIB") (part "KPT-2012SRC-PRV"))
    )
    (comp (ref "LED234")
      (value "KPT-2012SRC-PRV")
      (footprint "0805_LED")
      (libsource (lib "2008_SablierElectronique_SCHLIB") (part "KPT-2012SRC-PRV"))
    )
    (comp (ref "LED235")
      (value "KPT-2012SRC-PRV")
      (footprint "0805_LED")
      (libsource (lib "2008_SablierElectronique_SCHLIB") (part "KPT-2012SRC-PRV"))
    )
    (comp (ref "LED236")
      (value "KPT-2012SRC-PRV")
      (footprint "0805_LED")
      (libsource (lib "2008_SablierElectronique_SCHLIB") (part "KPT-2012SRC-PRV"))
    )
    (comp (ref "LED237")
      (value "KPT-2012SRC-PRV")
      (footprint "0805_LED")
      (libsource (lib "2008_SablierElectronique_SCHLIB") (part "KPT-2012SRC-PRV"))
    )
    (comp (ref "LED238")
      (value "KPT-2012SRC-PRV")
      (footprint "0805_LED")
      (libsource (lib "2008_SablierElectronique_SCHLIB") (part "KPT-2012SRC-PRV"))
    )
    (comp (ref "LED239")
      (value "KPT-2012SRC-PRV")
      (footprint "0805_LED")
      (libsource (lib "2008_SablierElectronique_SCHLIB") (part "KPT-2012SRC-PRV"))
    )
    (comp (ref "LED240")
      (value "KPT-2012SRC-PRV")
      (footprint "0805_LED")
      (libsource (lib "2008_SablierElectronique_SCHLIB") (part "KPT-2012SRC-PRV"))
    )
    (comp (ref "LED241")
      (value "KPT-2012SRC-PRV")
      (footprint "0805_LED")
      (libsource (lib "2008_SablierElectronique_SCHLIB") (part "KPT-2012SRC-PRV"))
    )
    (comp (ref "LED242")
      (value "KPT-2012SRC-PRV")
      (footprint "0805_LED")
      (libsource (lib "2008_SablierElectronique_SCHLIB") (part "KPT-2012SRC-PRV"))
    )
    (comp (ref "LED243")
      (value "KPT-2012SRC-PRV")
      (footprint "0805_LED")
      (libsource (lib "2008_SablierElectronique_SCHLIB") (part "KPT-2012SRC-PRV"))
    )
    (comp (ref "LED244")
      (value "KPT-2012SRC-PRV")
      (footprint "0805_LED")
      (libsource (lib "2008_SablierElectronique_SCHLIB") (part "KPT-2012SRC-PRV"))
    )
    (comp (ref "LED245")
      (value "KPT-2012SRC-PRV")
      (footprint "0805_LED")
      (libsource (lib "2008_SablierElectronique_SCHLIB") (part "KPT-2012SRC-PRV"))
    )
    (comp (ref "LED246")
      (value "KPT-2012SRC-PRV")
      (footprint "0805_LED")
      (libsource (lib "2008_SablierElectronique_SCHLIB") (part "KPT-2012SRC-PRV"))
    )
    (comp (ref "LED247")
      (value "KPT-2012SRC-PRV")
      (footprint "0805_LED")
      (libsource (lib "2008_SablierElectronique_SCHLIB") (part "KPT-2012SRC-PRV"))
    )
    (comp (ref "LED248")
      (value "KPT-2012SRC-PRV")
      (footprint "0805_LED")
      (libsource (lib "2008_SablierElectronique_SCHLIB") (part "KPT-2012SRC-PRV"))
    )
    (comp (ref "LED249")
      (value "KPT-2012SRC-PRV")
      (footprint "0805_LED")
      (libsource (lib "2008_SablierElectronique_SCHLIB") (part "KPT-2012SRC-PRV"))
    )
    (comp (ref "LED250")
      (value "KPT-2012SRC-PRV")
      (footprint "0805_LED")
      (libsource (lib "2008_SablierElectronique_SCHLIB") (part "KPT-2012SRC-PRV"))
    )
    (comp (ref "LED251")
      (value "KPT-2012SRC-PRV")
      (footprint "0805_LED")
      (libsource (lib "2008_SablierElectronique_SCHLIB") (part "KPT-2012SRC-PRV"))
    )
    (comp (ref "LED252")
      (value "KPT-2012SRC-PRV")
      (footprint "0805_LED")
      (libsource (lib "2008_SablierElectronique_SCHLIB") (part "KPT-2012SRC-PRV"))
    )
    (comp (ref "LED253")
      (value "KPT-2012SRC-PRV")
      (footprint "0805_LED")
      (libsource (lib "2008_SablierElectronique_SCHLIB") (part "KPT-2012SRC-PRV"))
    )
    (comp (ref "LED254")
      (value "KPT-2012SRC-PRV")
      (footprint "0805_LED")
      (libsource (lib "2008_SablierElectronique_SCHLIB") (part "KPT-2012SRC-PRV"))
    )
    (comp (ref "LED255")
      (value "KPT-2012SRC-PRV")
      (footprint "0805_LED")
      (libsource (lib "2008_SablierElectronique_SCHLIB") (part "KPT-2012SRC-PRV"))
    )
    (comp (ref "LED256")
      (value "KPT-2012SRC-PRV")
      (footprint "0805_LED")
      (libsource (lib "2008_SablierElectronique_SCHLIB") (part "KPT-2012SRC-PRV"))
    )
    (comp (ref "X1")
      (value "Anodes")
      (footprint "CON8x8(edited)")
      (libsource (lib "") (part "Mâle DIN 8 x 8_1"))
    )
    (comp (ref "X2")
      (value "Cathodes")
      (footprint "CON8x8(edited)")
      (libsource (lib "2008_SablierElectronique_SCHLIB") (part "Mâle DIN 8 x 8"))
    )
  )
  (nets
    (net (code "1") (name "Net-(LED1-A)") (class "Default")
      (node (ref "LED1") (pin "2") (pinfunction "A_2") (pintype "passive"))
      (node (ref "LED113") (pin "2") (pinfunction "A_2") (pintype "passive"))
      (node (ref "LED129") (pin "2") (pinfunction "A_2") (pintype "passive"))
      (node (ref "LED145") (pin "2") (pinfunction "A_2") (pintype "passive"))
      (node (ref "LED161") (pin "2") (pinfunction "A_2") (pintype "passive"))
      (node (ref "LED17") (pin "2") (pinfunction "A_2") (pintype "passive"))
      (node (ref "LED177") (pin "2") (pinfunction "A_2") (pintype "passive"))
      (node (ref "LED193") (pin "2") (pinfunction "A_2") (pintype "passive"))
      (node (ref "LED209") (pin "2") (pinfunction "A_2") (pintype "passive"))
      (node (ref "LED225") (pin "2") (pinfunction "A_2") (pintype "passive"))
      (node (ref "LED241") (pin "2") (pinfunction "A_2") (pintype "passive"))
      (node (ref "LED33") (pin "2") (pinfunction "A_2") (pintype "passive"))
      (node (ref "LED49") (pin "2") (pinfunction "A_2") (pintype "passive"))
      (node (ref "LED65") (pin "2") (pinfunction "A_2") (pintype "passive"))
      (node (ref "LED81") (pin "2") (pinfunction "A_2") (pintype "passive"))
      (node (ref "LED97") (pin "2") (pinfunction "A_2") (pintype "passive"))
      (node (ref "X1") (pin "1") (pinfunction "1_1") (pintype "passive"))
    )
    (net (code "2") (name "Net-(LED1-K)") (class "Default")
      (node (ref "LED1") (pin "1") (pinfunction "K_1") (pintype "passive"))
      (node (ref "LED10") (pin "1") (pinfunction "K_1") (pintype "passive"))
      (node (ref "LED11") (pin "1") (pinfunction "K_1") (pintype "passive"))
      (node (ref "LED12") (pin "1") (pinfunction "K_1") (pintype "passive"))
      (node (ref "LED13") (pin "1") (pinfunction "K_1") (pintype "passive"))
      (node (ref "LED14") (pin "1") (pinfunction "K_1") (pintype "passive"))
      (node (ref "LED15") (pin "1") (pinfunction "K_1") (pintype "passive"))
      (node (ref "LED16") (pin "1") (pinfunction "K_1") (pintype "passive"))
      (node (ref "LED2") (pin "1") (pinfunction "K_1") (pintype "passive"))
      (node (ref "LED3") (pin "1") (pinfunction "K_1") (pintype "passive"))
      (node (ref "LED4") (pin "1") (pinfunction "K_1") (pintype "passive"))
      (node (ref "LED5") (pin "1") (pinfunction "K_1") (pintype "passive"))
      (node (ref "LED6") (pin "1") (pinfunction "K_1") (pintype "passive"))
      (node (ref "LED7") (pin "1") (pinfunction "K_1") (pintype "passive"))
      (node (ref "LED8") (pin "1") (pinfunction "K_1") (pintype "passive"))
      (node (ref "LED9") (pin "1") (pinfunction "K_1") (pintype "passive"))
      (node (ref "X2") (pin "1") (pinfunction "1_1") (pintype "passive"))
    )
    (net (code "3") (name "Net-(LED10-A)") (class "Default")
      (node (ref "LED10") (pin "2") (pinfunction "A_2") (pintype "passive"))
      (node (ref "LED106") (pin "2") (pinfunction "A_2") (pintype "passive"))
      (node (ref "LED122") (pin "2") (pinfunction "A_2") (pintype "passive"))
      (node (ref "LED138") (pin "2") (pinfunction "A_2") (pintype "passive"))
      (node (ref "LED154") (pin "2") (pinfunction "A_2") (pintype "passive"))
      (node (ref "LED170") (pin "2") (pinfunction "A_2") (pintype "passive"))
      (node (ref "LED186") (pin "2") (pinfunction "A_2") (pintype "passive"))
      (node (ref "LED202") (pin "2") (pinfunction "A_2") (pintype "passive"))
      (node (ref "LED218") (pin "2") (pinfunction "A_2") (pintype "passive"))
      (node (ref "LED234") (pin "2") (pinfunction "A_2") (pintype "passive"))
      (node (ref "LED250") (pin "2") (pinfunction "A_2") (pintype "passive"))
      (node (ref "LED26") (pin "2") (pinfunction "A_2") (pintype "passive"))
      (node (ref "LED42") (pin "2") (pinfunction "A_2") (pintype "passive"))
      (node (ref "LED58") (pin "2") (pinfunction "A_2") (pintype "passive"))
      (node (ref "LED74") (pin "2") (pinfunction "A_2") (pintype "passive"))
      (node (ref "LED90") (pin "2") (pinfunction "A_2") (pintype "passive"))
      (node (ref "X1") (pin "10") (pinfunction "10_10") (pintype "passive"))
    )
    (net (code "4") (name "Net-(LED17-K)") (class "Default")
      (node (ref "LED17") (pin "1") (pinfunction "K_1") (pintype "passive"))
      (node (ref "LED18") (pin "1") (pinfunction "K_1") (pintype "passive"))
      (node (ref "LED19") (pin "1") (pinfunction "K_1") (pintype "passive"))
      (node (ref "LED20") (pin "1") (pinfunction "K_1") (pintype "passive"))
      (node (ref "LED21") (pin "1") (pinfunction "K_1") (pintype "passive"))
      (node (ref "LED22") (pin "1") (pinfunction "K_1") (pintype "passive"))
      (node (ref "LED23") (pin "1") (pinfunction "K_1") (pintype "passive"))
      (node (ref "LED24") (pin "1") (pinfunction "K_1") (pintype "passive"))
      (node (ref "LED25") (pin "1") (pinfunction "K_1") (pintype "passive"))
      (node (ref "LED26") (pin "1") (pinfunction "K_1") (pintype "passive"))
      (node (ref "LED27") (pin "1") (pinfunction "K_1") (pintype "passive"))
      (node (ref "LED28") (pin "1") (pinfunction "K_1") (pintype "passive"))
      (node (ref "LED29") (pin "1") (pinfunction "K_1") (pintype "passive"))
      (node (ref "LED30") (pin "1") (pinfunction "K_1") (pintype "passive"))
      (node (ref "LED31") (pin "1") (pinfunction "K_1") (pintype "passive"))
      (node (ref "LED32") (pin "1") (pinfunction "K_1") (pintype "passive"))
      (node (ref "X2") (pin "2") (pinfunction "2_2") (pintype "passive"))
    )
    (net (code "5") (name "Net-(LED33-K)") (class "Default")
      (node (ref "LED33") (pin "1") (pinfunction "K_1") (pintype "passive"))
      (node (ref "LED34") (pin "1") (pinfunction "K_1") (pintype "passive"))
      (node (ref "LED35") (pin "1") (pinfunction "K_1") (pintype "passive"))
      (node (ref "LED36") (pin "1") (pinfunction "K_1") (pintype "passive"))
      (node (ref "LED37") (pin "1") (pinfunction "K_1") (pintype "passive"))
      (node (ref "LED38") (pin "1") (pinfunction "K_1") (pintype "passive"))
      (node (ref "LED39") (pin "1") (pinfunction "K_1") (pintype "passive"))
      (node (ref "LED40") (pin "1") (pinfunction "K_1") (pintype "passive"))
      (node (ref "LED41") (pin "1") (pinfunction "K_1") (pintype "passive"))
      (node (ref "LED42") (pin "1") (pinfunction "K_1") (pintype "passive"))
      (node (ref "LED43") (pin "1") (pinfunction "K_1") (pintype "passive"))
      (node (ref "LED44") (pin "1") (pinfunction "K_1") (pintype "passive"))
      (node (ref "LED45") (pin "1") (pinfunction "K_1") (pintype "passive"))
      (node (ref "LED46") (pin "1") (pinfunction "K_1") (pintype "passive"))
      (node (ref "LED47") (pin "1") (pinfunction "K_1") (pintype "passive"))
      (node (ref "LED48") (pin "1") (pinfunction "K_1") (pintype "passive"))
      (node (ref "X2") (pin "3") (pinfunction "3_3") (pintype "passive"))
    )
    (net (code "6") (name "Net-(LED49-K)") (class "Default")
      (node (ref "LED49") (pin "1") (pinfunction "K_1") (pintype "passive"))
      (node (ref "LED50") (pin "1") (pinfunction "K_1") (pintype "passive"))
      (node (ref "LED51") (pin "1") (pinfunction "K_1") (pintype "passive"))
      (node (ref "LED52") (pin "1") (pinfunction "K_1") (pintype "passive"))
      (node (ref "LED53") (pin "1") (pinfunction "K_1") (pintype "passive"))
      (node (ref "LED54") (pin "1") (pinfunction "K_1") (pintype "passive"))
      (node (ref "LED55") (pin "1") (pinfunction "K_1") (pintype "passive"))
      (node (ref "LED56") (pin "1") (pinfunction "K_1") (pintype "passive"))
      (node (ref "LED57") (pin "1") (pinfunction "K_1") (pintype "passive"))
      (node (ref "LED58") (pin "1") (pinfunction "K_1") (pintype "passive"))
      (node (ref "LED59") (pin "1") (pinfunction "K_1") (pintype "passive"))
      (node (ref "LED60") (pin "1") (pinfunction "K_1") (pintype "passive"))
      (node (ref "LED61") (pin "1") (pinfunction "K_1") (pintype "passive"))
      (node (ref "LED62") (pin "1") (pinfunction "K_1") (pintype "passive"))
      (node (ref "LED63") (pin "1") (pinfunction "K_1") (pintype "passive"))
      (node (ref "LED64") (pin "1") (pinfunction "K_1") (pintype "passive"))
      (node (ref "X2") (pin "4") (pinfunction "4_4") (pintype "passive"))
    )
    (net (code "7") (name "Net-(LED65-K)") (class "Default")
      (node (ref "LED65") (pin "1") (pinfunction "K_1") (pintype "passive"))
      (node (ref "LED66") (pin "1") (pinfunction "K_1") (pintype "passive"))
      (node (ref "LED67") (pin "1") (pinfunction "K_1") (pintype "passive"))
      (node (ref "LED68") (pin "1") (pinfunction "K_1") (pintype "passive"))
      (node (ref "LED69") (pin "1") (pinfunction "K_1") (pintype "passive"))
      (node (ref "LED70") (pin "1") (pinfunction "K_1") (pintype "passive"))
      (node (ref "LED71") (pin "1") (pinfunction "K_1") (pintype "passive"))
      (node (ref "LED72") (pin "1") (pinfunction "K_1") (pintype "passive"))
      (node (ref "LED73") (pin "1") (pinfunction "K_1") (pintype "passive"))
      (node (ref "LED74") (pin "1") (pinfunction "K_1") (pintype "passive"))
      (node (ref "LED75") (pin "1") (pinfunction "K_1") (pintype "passive"))
      (node (ref "LED76") (pin "1") (pinfunction "K_1") (pintype "passive"))
      (node (ref "LED77") (pin "1") (pinfunction "K_1") (pintype "passive"))
      (node (ref "LED78") (pin "1") (pinfunction "K_1") (pintype "passive"))
      (node (ref "LED79") (pin "1") (pinfunction "K_1") (pintype "passive"))
      (node (ref "LED80") (pin "1") (pinfunction "K_1") (pintype "passive"))
      (node (ref "X2") (pin "5") (pinfunction "5_5") (pintype "passive"))
    )
    (net (code "8") (name "Net-(LED81-K)") (class "Default")
      (node (ref "LED81") (pin "1") (pinfunction "K_1") (pintype "passive"))
      (node (ref "LED82") (pin "1") (pinfunction "K_1") (pintype "passive"))
      (node (ref "LED83") (pin "1") (pinfunction "K_1") (pintype "passive"))
      (node (ref "LED84") (pin "1") (pinfunction "K_1") (pintype "passive"))
      (node (ref "LED85") (pin "1") (pinfunction "K_1") (pintype "passive"))
      (node (ref "LED86") (pin "1") (pinfunction "K_1") (pintype "passive"))
      (node (ref "LED87") (pin "1") (pinfunction "K_1") (pintype "passive"))
      (node (ref "LED88") (pin "1") (pinfunction "K_1") (pintype "passive"))
      (node (ref "LED89") (pin "1") (pinfunction "K_1") (pintype "passive"))
      (node (ref "LED90") (pin "1") (pinfunction "K_1") (pintype "passive"))
      (node (ref "LED91") (pin "1") (pinfunction "K_1") (pintype "passive"))
      (node (ref "LED92") (pin "1") (pinfunction "K_1") (pintype "passive"))
      (node (ref "LED93") (pin "1") (pinfunction "K_1") (pintype "passive"))
      (node (ref "LED94") (pin "1") (pinfunction "K_1") (pintype "passive"))
      (node (ref "LED95") (pin "1") (pinfunction "K_1") (pintype "passive"))
      (node (ref "LED96") (pin "1") (pinfunction "K_1") (pintype "passive"))
      (node (ref "X2") (pin "6") (pinfunction "6_6") (pintype "passive"))
    )
    (net (code "9") (name "Net-(LED100-A)") (class "Default")
      (node (ref "LED100") (pin "2") (pinfunction "A_2") (pintype "passive"))
      (node (ref "LED116") (pin "2") (pinfunction "A_2") (pintype "passive"))
      (node (ref "LED132") (pin "2") (pinfunction "A_2") (pintype "passive"))
      (node (ref "LED148") (pin "2") (pinfunction "A_2") (pintype "passive"))
      (node (ref "LED164") (pin "2") (pinfunction "A_2") (pintype "passive"))
      (node (ref "LED180") (pin "2") (pinfunction "A_2") (pintype "passive"))
      (node (ref "LED196") (pin "2") (pinfunction "A_2") (pintype "passive"))
      (node (ref "LED20") (pin "2") (pinfunction "A_2") (pintype "passive"))
      (node (ref "LED212") (pin "2") (pinfunction "A_2") (pintype "passive"))
      (node (ref "LED228") (pin "2") (pinfunction "A_2") (pintype "passive"))
      (node (ref "LED244") (pin "2") (pinfunction "A_2") (pintype "passive"))
      (node (ref "LED36") (pin "2") (pinfunction "A_2") (pintype "passive"))
      (node (ref "LED4") (pin "2") (pinfunction "A_2") (pintype "passive"))
      (node (ref "LED52") (pin "2") (pinfunction "A_2") (pintype "passive"))
      (node (ref "LED68") (pin "2") (pinfunction "A_2") (pintype "passive"))
      (node (ref "LED84") (pin "2") (pinfunction "A_2") (pintype "passive"))
      (node (ref "X1") (pin "4") (pinfunction "4_4") (pintype "passive"))
    )
    (net (code "10") (name "Net-(LED100-K)") (class "Default")
      (node (ref "LED100") (pin "1") (pinfunction "K_1") (pintype "passive"))
      (node (ref "LED101") (pin "1") (pinfunction "K_1") (pintype "passive"))
      (node (ref "LED102") (pin "1") (pinfunction "K_1") (pintype "passive"))
      (node (ref "LED103") (pin "1") (pinfunction "K_1") (pintype "passive"))
      (node (ref "LED104") (pin "1") (pinfunction "K_1") (pintype "passive"))
      (node (ref "LED105") (pin "1") (pinfunction "K_1") (pintype "passive"))
      (node (ref "LED106") (pin "1") (pinfunction "K_1") (pintype "passive"))
      (node (ref "LED107") (pin "1") (pinfunction "K_1") (pintype "passive"))
      (node (ref "LED108") (pin "1") (pinfunction "K_1") (pintype "passive"))
      (node (ref "LED109") (pin "1") (pinfunction "K_1") (pintype "passive"))
      (node (ref "LED110") (pin "1") (pinfunction "K_1") (pintype "passive"))
      (node (ref "LED111") (pin "1") (pinfunction "K_1") (pintype "passive"))
      (node (ref "LED112") (pin "1") (pinfunction "K_1") (pintype "passive"))
      (node (ref "LED97") (pin "1") (pinfunction "K_1") (pintype "passive"))
      (node (ref "LED98") (pin "1") (pinfunction "K_1") (pintype "passive"))
      (node (ref "LED99") (pin "1") (pinfunction "K_1") (pintype "passive"))
      (node (ref "X2") (pin "7") (pinfunction "7_7") (pintype "passive"))
    )
    (net (code "11") (name "Net-(LED101-A)") (class "Default")
      (node (ref "LED101") (pin "2") (pinfunction "A_2") (pintype "passive"))
      (node (ref "LED117") (pin "2") (pinfunction "A_2") (pintype "passive"))
      (node (ref "LED133") (pin "2") (pinfunction "A_2") (pintype "passive"))
      (node (ref "LED149") (pin "2") (pinfunction "A_2") (pintype "passive"))
      (node (ref "LED165") (pin "2") (pinfunction "A_2") (pintype "passive"))
      (node (ref "LED181") (pin "2") (pinfunction "A_2") (pintype "passive"))
      (node (ref "LED197") (pin "2") (pinfunction "A_2") (pintype "passive"))
      (node (ref "LED21") (pin "2") (pinfunction "A_2") (pintype "passive"))
      (node (ref "LED213") (pin "2") (pinfunction "A_2") (pintype "passive"))
      (node (ref "LED229") (pin "2") (pinfunction "A_2") (pintype "passive"))
      (node (ref "LED245") (pin "2") (pinfunction "A_2") (pintype "passive"))
      (node (ref "LED37") (pin "2") (pinfunction "A_2") (pintype "passive"))
      (node (ref "LED5") (pin "2") (pinfunction "A_2") (pintype "passive"))
      (node (ref "LED53") (pin "2") (pinfunction "A_2") (pintype "passive"))
      (node (ref "LED69") (pin "2") (pinfunction "A_2") (pintype "passive"))
      (node (ref "LED85") (pin "2") (pinfunction "A_2") (pintype "passive"))
      (node (ref "X1") (pin "5") (pinfunction "5_5") (pintype "passive"))
    )
    (net (code "12") (name "Net-(LED102-A)") (class "Default")
      (node (ref "LED102") (pin "2") (pinfunction "A_2") (pintype "passive"))
      (node (ref "LED118") (pin "2") (pinfunction "A_2") (pintype "passive"))
      (node (ref "LED134") (pin "2") (pinfunction "A_2") (pintype "passive"))
      (node (ref "LED150") (pin "2") (pinfunction "A_2") (pintype "passive"))
      (node (ref "LED166") (pin "2") (pinfunction "A_2") (pintype "passive"))
      (node (ref "LED182") (pin "2") (pinfunction "A_2") (pintype "passive"))
      (node (ref "LED198") (pin "2") (pinfunction "A_2") (pintype "passive"))
      (node (ref "LED214") (pin "2") (pinfunction "A_2") (pintype "passive"))
      (node (ref "LED22") (pin "2") (pinfunction "A_2") (pintype "passive"))
      (node (ref "LED230") (pin "2") (pinfunction "A_2") (pintype "passive"))
      (node (ref "LED246") (pin "2") (pinfunction "A_2") (pintype "passive"))
      (node (ref "LED38") (pin "2") (pinfunction "A_2") (pintype "passive"))
      (node (ref "LED54") (pin "2") (pinfunction "A_2") (pintype "passive"))
      (node (ref "LED6") (pin "2") (pinfunction "A_2") (pintype "passive"))
      (node (ref "LED70") (pin "2") (pinfunction "A_2") (pintype "passive"))
      (node (ref "LED86") (pin "2") (pinfunction "A_2") (pintype "passive"))
      (node (ref "X1") (pin "6") (pinfunction "6_6") (pintype "passive"))
    )
    (net (code "13") (name "Net-(LED103-A)") (class "Default")
      (node (ref "LED103") (pin "2") (pinfunction "A_2") (pintype "passive"))
      (node (ref "LED119") (pin "2") (pinfunction "A_2") (pintype "passive"))
      (node (ref "LED135") (pin "2") (pinfunction "A_2") (pintype "passive"))
      (node (ref "LED151") (pin "2") (pinfunction "A_2") (pintype "passive"))
      (node (ref "LED167") (pin "2") (pinfunction "A_2") (pintype "passive"))
      (node (ref "LED183") (pin "2") (pinfunction "A_2") (pintype "passive"))
      (node (ref "LED199") (pin "2") (pinfunction "A_2") (pintype "passive"))
      (node (ref "LED215") (pin "2") (pinfunction "A_2") (pintype "passive"))
      (node (ref "LED23") (pin "2") (pinfunction "A_2") (pintype "passive"))
      (node (ref "LED231") (pin "2") (pinfunction "A_2") (pintype "passive"))
      (node (ref "LED247") (pin "2") (pinfunction "A_2") (pintype "passive"))
      (node (ref "LED39") (pin "2") (pinfunction "A_2") (pintype "passive"))
      (node (ref "LED55") (pin "2") (pinfunction "A_2") (pintype "passive"))
      (node (ref "LED7") (pin "2") (pinfunction "A_2") (pintype "passive"))
      (node (ref "LED71") (pin "2") (pinfunction "A_2") (pintype "passive"))
      (node (ref "LED87") (pin "2") (pinfunction "A_2") (pintype "passive"))
      (node (ref "X1") (pin "7") (pinfunction "7_7") (pintype "passive"))
    )
    (net (code "14") (name "Net-(LED104-A)") (class "Default")
      (node (ref "LED104") (pin "2") (pinfunction "A_2") (pintype "passive"))
      (node (ref "LED120") (pin "2") (pinfunction "A_2") (pintype "passive"))
      (node (ref "LED136") (pin "2") (pinfunction "A_2") (pintype "passive"))
      (node (ref "LED152") (pin "2") (pinfunction "A_2") (pintype "passive"))
      (node (ref "LED168") (pin "2") (pinfunction "A_2") (pintype "passive"))
      (node (ref "LED184") (pin "2") (pinfunction "A_2") (pintype "passive"))
      (node (ref "LED200") (pin "2") (pinfunction "A_2") (pintype "passive"))
      (node (ref "LED216") (pin "2") (pinfunction "A_2") (pintype "passive"))
      (node (ref "LED232") (pin "2") (pinfunction "A_2") (pintype "passive"))
      (node (ref "LED24") (pin "2") (pinfunction "A_2") (pintype "passive"))
      (node (ref "LED248") (pin "2") (pinfunction "A_2") (pintype "passive"))
      (node (ref "LED40") (pin "2") (pinfunction "A_2") (pintype "passive"))
      (node (ref "LED56") (pin "2") (pinfunction "A_2") (pintype "passive"))
      (node (ref "LED72") (pin "2") (pinfunction "A_2") (pintype "passive"))
      (node (ref "LED8") (pin "2") (pinfunction "A_2") (pintype "passive"))
      (node (ref "LED88") (pin "2") (pinfunction "A_2") (pintype "passive"))
      (node (ref "X1") (pin "8") (pinfunction "8_8") (pintype "passive"))
    )
    (net (code "15") (name "Net-(LED105-A)") (class "Default")
      (node (ref "LED105") (pin "2") (pinfunction "A_2") (pintype "passive"))
      (node (ref "LED121") (pin "2") (pinfunction "A_2") (pintype "passive"))
      (node (ref "LED137") (pin "2") (pinfunction "A_2") (pintype "passive"))
      (node (ref "LED153") (pin "2") (pinfunction "A_2") (pintype "passive"))
      (node (ref "LED169") (pin "2") (pinfunction "A_2") (pintype "passive"))
      (node (ref "LED185") (pin "2") (pinfunction "A_2") (pintype "passive"))
      (node (ref "LED201") (pin "2") (pinfunction "A_2") (pintype "passive"))
      (node (ref "LED217") (pin "2") (pinfunction "A_2") (pintype "passive"))
      (node (ref "LED233") (pin "2") (pinfunction "A_2") (pintype "passive"))
      (node (ref "LED249") (pin "2") (pinfunction "A_2") (pintype "passive"))
      (node (ref "LED25") (pin "2") (pinfunction "A_2") (pintype "passive"))
      (node (ref "LED41") (pin "2") (pinfunction "A_2") (pintype "passive"))
      (node (ref "LED57") (pin "2") (pinfunction "A_2") (pintype "passive"))
      (node (ref "LED73") (pin "2") (pinfunction "A_2") (pintype "passive"))
      (node (ref "LED89") (pin "2") (pinfunction "A_2") (pintype "passive"))
      (node (ref "LED9") (pin "2") (pinfunction "A_2") (pintype "passive"))
      (node (ref "X1") (pin "9") (pinfunction "9_9") (pintype "passive"))
    )
    (net (code "16") (name "Net-(LED107-A)") (class "Default")
      (node (ref "LED107") (pin "2") (pinfunction "A_2") (pintype "passive"))
      (node (ref "LED11") (pin "2") (pinfunction "A_2") (pintype "passive"))
      (node (ref "LED123") (pin "2") (pinfunction "A_2") (pintype "passive"))
      (node (ref "LED139") (pin "2") (pinfunction "A_2") (pintype "passive"))
      (node (ref "LED155") (pin "2") (pinfunction "A_2") (pintype "passive"))
      (node (ref "LED171") (pin "2") (pinfunction "A_2") (pintype "passive"))
      (node (ref "LED187") (pin "2") (pinfunction "A_2") (pintype "passive"))
      (node (ref "LED203") (pin "2") (pinfunction "A_2") (pintype "passive"))
      (node (ref "LED219") (pin "2") (pinfunction "A_2") (pintype "passive"))
      (node (ref "LED235") (pin "2") (pinfunction "A_2") (pintype "passive"))
      (node (ref "LED251") (pin "2") (pinfunction "A_2") (pintype "passive"))
      (node (ref "LED27") (pin "2") (pinfunction "A_2") (pintype "passive"))
      (node (ref "LED43") (pin "2") (pinfunction "A_2") (pintype "passive"))
      (node (ref "LED59") (pin "2") (pinfunction "A_2") (pintype "passive"))
      (node (ref "LED75") (pin "2") (pinfunction "A_2") (pintype "passive"))
      (node (ref "LED91") (pin "2") (pinfunction "A_2") (pintype "passive"))
      (node (ref "X1") (pin "11") (pinfunction "11_11") (pintype "passive"))
    )
    (net (code "17") (name "Net-(LED108-A)") (class "Default")
      (node (ref "LED108") (pin "2") (pinfunction "A_2") (pintype "passive"))
      (node (ref "LED12") (pin "2") (pinfunction "A_2") (pintype "passive"))
      (node (ref "LED124") (pin "2") (pinfunction "A_2") (pintype "passive"))
      (node (ref "LED140") (pin "2") (pinfunction "A_2") (pintype "passive"))
      (node (ref "LED156") (pin "2") (pinfunction "A_2") (pintype "passive"))
      (node (ref "LED172") (pin "2") (pinfunction "A_2") (pintype "passive"))
      (node (ref "LED188") (pin "2") (pinfunction "A_2") (pintype "passive"))
      (node (ref "LED204") (pin "2") (pinfunction "A_2") (pintype "passive"))
      (node (ref "LED220") (pin "2") (pinfunction "A_2") (pintype "passive"))
      (node (ref "LED236") (pin "2") (pinfunction "A_2") (pintype "passive"))
      (node (ref "LED252") (pin "2") (pinfunction "A_2") (pintype "passive"))
      (node (ref "LED28") (pin "2") (pinfunction "A_2") (pintype "passive"))
      (node (ref "LED44") (pin "2") (pinfunction "A_2") (pintype "passive"))
      (node (ref "LED60") (pin "2") (pinfunction "A_2") (pintype "passive"))
      (node (ref "LED76") (pin "2") (pinfunction "A_2") (pintype "passive"))
      (node (ref "LED92") (pin "2") (pinfunction "A_2") (pintype "passive"))
      (node (ref "X1") (pin "12") (pinfunction "12_12") (pintype "passive"))
    )
    (net (code "18") (name "Net-(LED109-A)") (class "Default")
      (node (ref "LED109") (pin "2") (pinfunction "A_2") (pintype "passive"))
      (node (ref "LED125") (pin "2") (pinfunction "A_2") (pintype "passive"))
      (node (ref "LED13") (pin "2") (pinfunction "A_2") (pintype "passive"))
      (node (ref "LED141") (pin "2") (pinfunction "A_2") (pintype "passive"))
      (node (ref "LED157") (pin "2") (pinfunction "A_2") (pintype "passive"))
      (node (ref "LED173") (pin "2") (pinfunction "A_2") (pintype "passive"))
      (node (ref "LED189") (pin "2") (pinfunction "A_2") (pintype "passive"))
      (node (ref "LED205") (pin "2") (pinfunction "A_2") (pintype "passive"))
      (node (ref "LED221") (pin "2") (pinfunction "A_2") (pintype "passive"))
      (node (ref "LED237") (pin "2") (pinfunction "A_2") (pintype "passive"))
      (node (ref "LED253") (pin "2") (pinfunction "A_2") (pintype "passive"))
      (node (ref "LED29") (pin "2") (pinfunction "A_2") (pintype "passive"))
      (node (ref "LED45") (pin "2") (pinfunction "A_2") (pintype "passive"))
      (node (ref "LED61") (pin "2") (pinfunction "A_2") (pintype "passive"))
      (node (ref "LED77") (pin "2") (pinfunction "A_2") (pintype "passive"))
      (node (ref "LED93") (pin "2") (pinfunction "A_2") (pintype "passive"))
      (node (ref "X1") (pin "13") (pinfunction "13_13") (pintype "passive"))
    )
    (net (code "19") (name "Net-(LED110-A)") (class "Default")
      (node (ref "LED110") (pin "2") (pinfunction "A_2") (pintype "passive"))
      (node (ref "LED126") (pin "2") (pinfunction "A_2") (pintype "passive"))
      (node (ref "LED14") (pin "2") (pinfunction "A_2") (pintype "passive"))
      (node (ref "LED142") (pin "2") (pinfunction "A_2") (pintype "passive"))
      (node (ref "LED158") (pin "2") (pinfunction "A_2") (pintype "passive"))
      (node (ref "LED174") (pin "2") (pinfunction "A_2") (pintype "passive"))
      (node (ref "LED190") (pin "2") (pinfunction "A_2") (pintype "passive"))
      (node (ref "LED206") (pin "2") (pinfunction "A_2") (pintype "passive"))
      (node (ref "LED222") (pin "2") (pinfunction "A_2") (pintype "passive"))
      (node (ref "LED238") (pin "2") (pinfunction "A_2") (pintype "passive"))
      (node (ref "LED254") (pin "2") (pinfunction "A_2") (pintype "passive"))
      (node (ref "LED30") (pin "2") (pinfunction "A_2") (pintype "passive"))
      (node (ref "LED46") (pin "2") (pinfunction "A_2") (pintype "passive"))
      (node (ref "LED62") (pin "2") (pinfunction "A_2") (pintype "passive"))
      (node (ref "LED78") (pin "2") (pinfunction "A_2") (pintype "passive"))
      (node (ref "LED94") (pin "2") (pinfunction "A_2") (pintype "passive"))
      (node (ref "X1") (pin "14") (pinfunction "14_14") (pintype "passive"))
    )
    (net (code "20") (name "Net-(LED111-A)") (class "Default")
      (node (ref "LED111") (pin "2") (pinfunction "A_2") (pintype "passive"))
      (node (ref "LED127") (pin "2") (pinfunction "A_2") (pintype "passive"))
      (node (ref "LED143") (pin "2") (pinfunction "A_2") (pintype "passive"))
      (node (ref "LED15") (pin "2") (pinfunction "A_2") (pintype "passive"))
      (node (ref "LED159") (pin "2") (pinfunction "A_2") (pintype "passive"))
      (node (ref "LED175") (pin "2") (pinfunction "A_2") (pintype "passive"))
      (node (ref "LED191") (pin "2") (pinfunction "A_2") (pintype "passive"))
      (node (ref "LED207") (pin "2") (pinfunction "A_2") (pintype "passive"))
      (node (ref "LED223") (pin "2") (pinfunction "A_2") (pintype "passive"))
      (node (ref "LED239") (pin "2") (pinfunction "A_2") (pintype "passive"))
      (node (ref "LED255") (pin "2") (pinfunction "A_2") (pintype "passive"))
      (node (ref "LED31") (pin "2") (pinfunction "A_2") (pintype "passive"))
      (node (ref "LED47") (pin "2") (pinfunction "A_2") (pintype "passive"))
      (node (ref "LED63") (pin "2") (pinfunction "A_2") (pintype "passive"))
      (node (ref "LED79") (pin "2") (pinfunction "A_2") (pintype "passive"))
      (node (ref "LED95") (pin "2") (pinfunction "A_2") (pintype "passive"))
      (node (ref "X1") (pin "15") (pinfunction "15_15") (pintype "passive"))
    )
    (net (code "21") (name "Net-(LED112-A)") (class "Default")
      (node (ref "LED112") (pin "2") (pinfunction "A_2") (pintype "passive"))
      (node (ref "LED128") (pin "2") (pinfunction "A_2") (pintype "passive"))
      (node (ref "LED144") (pin "2") (pinfunction "A_2") (pintype "passive"))
      (node (ref "LED16") (pin "2") (pinfunction "A_2") (pintype "passive"))
      (node (ref "LED160") (pin "2") (pinfunction "A_2") (pintype "passive"))
      (node (ref "LED176") (pin "2") (pinfunction "A_2") (pintype "passive"))
      (node (ref "LED192") (pin "2") (pinfunction "A_2") (pintype "passive"))
      (node (ref "LED208") (pin "2") (pinfunction "A_2") (pintype "passive"))
      (node (ref "LED224") (pin "2") (pinfunction "A_2") (pintype "passive"))
      (node (ref "LED240") (pin "2") (pinfunction "A_2") (pintype "passive"))
      (node (ref "LED256") (pin "2") (pinfunction "A_2") (pintype "passive"))
      (node (ref "LED32") (pin "2") (pinfunction "A_2") (pintype "passive"))
      (node (ref "LED48") (pin "2") (pinfunction "A_2") (pintype "passive"))
      (node (ref "LED64") (pin "2") (pinfunction "A_2") (pintype "passive"))
      (node (ref "LED80") (pin "2") (pinfunction "A_2") (pintype "passive"))
      (node (ref "LED96") (pin "2") (pinfunction "A_2") (pintype "passive"))
      (node (ref "X1") (pin "16") (pinfunction "16_16") (pintype "passive"))
    )
    (net (code "22") (name "Net-(LED113-K)") (class "Default")
      (node (ref "LED113") (pin "1") (pinfunction "K_1") (pintype "passive"))
      (node (ref "LED114") (pin "1") (pinfunction "K_1") (pintype "passive"))
      (node (ref "LED115") (pin "1") (pinfunction "K_1") (pintype "passive"))
      (node (ref "LED116") (pin "1") (pinfunction "K_1") (pintype "passive"))
      (node (ref "LED117") (pin "1") (pinfunction "K_1") (pintype "passive"))
      (node (ref "LED118") (pin "1") (pinfunction "K_1") (pintype "passive"))
      (node (ref "LED119") (pin "1") (pinfunction "K_1") (pintype "passive"))
      (node (ref "LED120") (pin "1") (pinfunction "K_1") (pintype "passive"))
      (node (ref "LED121") (pin "1") (pinfunction "K_1") (pintype "passive"))
      (node (ref "LED122") (pin "1") (pinfunction "K_1") (pintype "passive"))
      (node (ref "LED123") (pin "1") (pinfunction "K_1") (pintype "passive"))
      (node (ref "LED124") (pin "1") (pinfunction "K_1") (pintype "passive"))
      (node (ref "LED125") (pin "1") (pinfunction "K_1") (pintype "passive"))
      (node (ref "LED126") (pin "1") (pinfunction "K_1") (pintype "passive"))
      (node (ref "LED127") (pin "1") (pinfunction "K_1") (pintype "passive"))
      (node (ref "LED128") (pin "1") (pinfunction "K_1") (pintype "passive"))
      (node (ref "X2") (pin "8") (pinfunction "8_8") (pintype "passive"))
    )
    (net (code "23") (name "Net-(LED114-A)") (class "Default")
      (node (ref "LED114") (pin "2") (pinfunction "A_2") (pintype "passive"))
      (node (ref "LED130") (pin "2") (pinfunction "A_2") (pintype "passive"))
      (node (ref "LED146") (pin "2") (pinfunction "A_2") (pintype "passive"))
      (node (ref "LED162") (pin "2") (pinfunction "A_2") (pintype "passive"))
      (node (ref "LED178") (pin "2") (pinfunction "A_2") (pintype "passive"))
      (node (ref "LED18") (pin "2") (pinfunction "A_2") (pintype "passive"))
      (node (ref "LED194") (pin "2") (pinfunction "A_2") (pintype "passive"))
      (node (ref "LED2") (pin "2") (pinfunction "A_2") (pintype "passive"))
      (node (ref "LED210") (pin "2") (pinfunction "A_2") (pintype "passive"))
      (node (ref "LED226") (pin "2") (pinfunction "A_2") (pintype "passive"))
      (node (ref "LED242") (pin "2") (pinfunction "A_2") (pintype "passive"))
      (node (ref "LED34") (pin "2") (pinfunction "A_2") (pintype "passive"))
      (node (ref "LED50") (pin "2") (pinfunction "A_2") (pintype "passive"))
      (node (ref "LED66") (pin "2") (pinfunction "A_2") (pintype "passive"))
      (node (ref "LED82") (pin "2") (pinfunction "A_2") (pintype "passive"))
      (node (ref "LED98") (pin "2") (pinfunction "A_2") (pintype "passive"))
      (node (ref "X1") (pin "2") (pinfunction "2_2") (pintype "passive"))
    )
    (net (code "24") (name "Net-(LED115-A)") (class "Default")
      (node (ref "LED115") (pin "2") (pinfunction "A_2") (pintype "passive"))
      (node (ref "LED131") (pin "2") (pinfunction "A_2") (pintype "passive"))
      (node (ref "LED147") (pin "2") (pinfunction "A_2") (pintype "passive"))
      (node (ref "LED163") (pin "2") (pinfunction "A_2") (pintype "passive"))
      (node (ref "LED179") (pin "2") (pinfunction "A_2") (pintype "passive"))
      (node (ref "LED19") (pin "2") (pinfunction "A_2") (pintype "passive"))
      (node (ref "LED195") (pin "2") (pinfunction "A_2") (pintype "passive"))
      (node (ref "LED211") (pin "2") (pinfunction "A_2") (pintype "passive"))
      (node (ref "LED227") (pin "2") (pinfunction "A_2") (pintype "passive"))
      (node (ref "LED243") (pin "2") (pinfunction "A_2") (pintype "passive"))
      (node (ref "LED3") (pin "2") (pinfunction "A_2") (pintype "passive"))
      (node (ref "LED35") (pin "2") (pinfunction "A_2") (pintype "passive"))
      (node (ref "LED51") (pin "2") (pinfunction "A_2") (pintype "passive"))
      (node (ref "LED67") (pin "2") (pinfunction "A_2") (pintype "passive"))
      (node (ref "LED83") (pin "2") (pinfunction "A_2") (pintype "passive"))
      (node (ref "LED99") (pin "2") (pinfunction "A_2") (pintype "passive"))
      (node (ref "X1") (pin "3") (pinfunction "3_3") (pintype "passive"))
    )
    (net (code "25") (name "Net-(LED129-K)") (class "Default")
      (node (ref "LED129") (pin "1") (pinfunction "K_1") (pintype "passive"))
      (node (ref "LED130") (pin "1") (pinfunction "K_1") (pintype "passive"))
      (node (ref "LED131") (pin "1") (pinfunction "K_1") (pintype "passive"))
      (node (ref "LED132") (pin "1") (pinfunction "K_1") (pintype "passive"))
      (node (ref "LED133") (pin "1") (pinfunction "K_1") (pintype "passive"))
      (node (ref "LED134") (pin "1") (pinfunction "K_1") (pintype "passive"))
      (node (ref "LED135") (pin "1") (pinfunction "K_1") (pintype "passive"))
      (node (ref "LED136") (pin "1") (pinfunction "K_1") (pintype "passive"))
      (node (ref "LED137") (pin "1") (pinfunction "K_1") (pintype "passive"))
      (node (ref "LED138") (pin "1") (pinfunction "K_1") (pintype "passive"))
      (node (ref "LED139") (pin "1") (pinfunction "K_1") (pintype "passive"))
      (node (ref "LED140") (pin "1") (pinfunction "K_1") (pintype "passive"))
      (node (ref "LED141") (pin "1") (pinfunction "K_1") (pintype "passive"))
      (node (ref "LED142") (pin "1") (pinfunction "K_1") (pintype "passive"))
      (node (ref "LED143") (pin "1") (pinfunction "K_1") (pintype "passive"))
      (node (ref "LED144") (pin "1") (pinfunction "K_1") (pintype "passive"))
      (node (ref "X2") (pin "9") (pinfunction "9_9") (pintype "passive"))
    )
    (net (code "26") (name "Net-(LED145-K)") (class "Default")
      (node (ref "LED145") (pin "1") (pinfunction "K_1") (pintype "passive"))
      (node (ref "LED146") (pin "1") (pinfunction "K_1") (pintype "passive"))
      (node (ref "LED147") (pin "1") (pinfunction "K_1") (pintype "passive"))
      (node (ref "LED148") (pin "1") (pinfunction "K_1") (pintype "passive"))
      (node (ref "LED149") (pin "1") (pinfunction "K_1") (pintype "passive"))
      (node (ref "LED150") (pin "1") (pinfunction "K_1") (pintype "passive"))
      (node (ref "LED151") (pin "1") (pinfunction "K_1") (pintype "passive"))
      (node (ref "LED152") (pin "1") (pinfunction "K_1") (pintype "passive"))
      (node (ref "LED153") (pin "1") (pinfunction "K_1") (pintype "passive"))
      (node (ref "LED154") (pin "1") (pinfunction "K_1") (pintype "passive"))
      (node (ref "LED155") (pin "1") (pinfunction "K_1") (pintype "passive"))
      (node (ref "LED156") (pin "1") (pinfunction "K_1") (pintype "passive"))
      (node (ref "LED157") (pin "1") (pinfunction "K_1") (pintype "passive"))
      (node (ref "LED158") (pin "1") (pinfunction "K_1") (pintype "passive"))
      (node (ref "LED159") (pin "1") (pinfunction "K_1") (pintype "passive"))
      (node (ref "LED160") (pin "1") (pinfunction "K_1") (pintype "passive"))
      (node (ref "X2") (pin "10") (pinfunction "10_10") (pintype "passive"))
    )
    (net (code "27") (name "Net-(LED161-K)") (class "Default")
      (node (ref "LED161") (pin "1") (pinfunction "K_1") (pintype "passive"))
      (node (ref "LED162") (pin "1") (pinfunction "K_1") (pintype "passive"))
      (node (ref "LED163") (pin "1") (pinfunction "K_1") (pintype "passive"))
      (node (ref "LED164") (pin "1") (pinfunction "K_1") (pintype "passive"))
      (node (ref "LED165") (pin "1") (pinfunction "K_1") (pintype "passive"))
      (node (ref "LED166") (pin "1") (pinfunction "K_1") (pintype "passive"))
      (node (ref "LED167") (pin "1") (pinfunction "K_1") (pintype "passive"))
      (node (ref "LED168") (pin "1") (pinfunction "K_1") (pintype "passive"))
      (node (ref "LED169") (pin "1") (pinfunction "K_1") (pintype "passive"))
      (node (ref "LED170") (pin "1") (pinfunction "K_1") (pintype "passive"))
      (node (ref "LED171") (pin "1") (pinfunction "K_1") (pintype "passive"))
      (node (ref "LED172") (pin "1") (pinfunction "K_1") (pintype "passive"))
      (node (ref "LED173") (pin "1") (pinfunction "K_1") (pintype "passive"))
      (node (ref "LED174") (pin "1") (pinfunction "K_1") (pintype "passive"))
      (node (ref "LED175") (pin "1") (pinfunction "K_1") (pintype "passive"))
      (node (ref "LED176") (pin "1") (pinfunction "K_1") (pintype "passive"))
      (node (ref "X2") (pin "11") (pinfunction "11_11") (pintype "passive"))
    )
    (net (code "28") (name "Net-(LED177-K)") (class "Default")
      (node (ref "LED177") (pin "1") (pinfunction "K_1") (pintype "passive"))
      (node (ref "LED178") (pin "1") (pinfunction "K_1") (pintype "passive"))
      (node (ref "LED179") (pin "1") (pinfunction "K_1") (pintype "passive"))
      (node (ref "LED180") (pin "1") (pinfunction "K_1") (pintype "passive"))
      (node (ref "LED181") (pin "1") (pinfunction "K_1") (pintype "passive"))
      (node (ref "LED182") (pin "1") (pinfunction "K_1") (pintype "passive"))
      (node (ref "LED183") (pin "1") (pinfunction "K_1") (pintype "passive"))
      (node (ref "LED184") (pin "1") (pinfunction "K_1") (pintype "passive"))
      (node (ref "LED185") (pin "1") (pinfunction "K_1") (pintype "passive"))
      (node (ref "LED186") (pin "1") (pinfunction "K_1") (pintype "passive"))
      (node (ref "LED187") (pin "1") (pinfunction "K_1") (pintype "passive"))
      (node (ref "LED188") (pin "1") (pinfunction "K_1") (pintype "passive"))
      (node (ref "LED189") (pin "1") (pinfunction "K_1") (pintype "passive"))
      (node (ref "LED190") (pin "1") (pinfunction "K_1") (pintype "passive"))
      (node (ref "LED191") (pin "1") (pinfunction "K_1") (pintype "passive"))
      (node (ref "LED192") (pin "1") (pinfunction "K_1") (pintype "passive"))
      (node (ref "X2") (pin "12") (pinfunction "12_12") (pintype "passive"))
    )
    (net (code "29") (name "Net-(LED193-K)") (class "Default")
      (node (ref "LED193") (pin "1") (pinfunction "K_1") (pintype "passive"))
      (node (ref "LED194") (pin "1") (pinfunction "K_1") (pintype "passive"))
      (node (ref "LED195") (pin "1") (pinfunction "K_1") (pintype "passive"))
      (node (ref "LED196") (pin "1") (pinfunction "K_1") (pintype "passive"))
      (node (ref "LED197") (pin "1") (pinfunction "K_1") (pintype "passive"))
      (node (ref "LED198") (pin "1") (pinfunction "K_1") (pintype "passive"))
      (node (ref "LED199") (pin "1") (pinfunction "K_1") (pintype "passive"))
      (node (ref "LED200") (pin "1") (pinfunction "K_1") (pintype "passive"))
      (node (ref "LED201") (pin "1") (pinfunction "K_1") (pintype "passive"))
      (node (ref "LED202") (pin "1") (pinfunction "K_1") (pintype "passive"))
      (node (ref "LED203") (pin "1") (pinfunction "K_1") (pintype "passive"))
      (node (ref "LED204") (pin "1") (pinfunction "K_1") (pintype "passive"))
      (node (ref "LED205") (pin "1") (pinfunction "K_1") (pintype "passive"))
      (node (ref "LED206") (pin "1") (pinfunction "K_1") (pintype "passive"))
      (node (ref "LED207") (pin "1") (pinfunction "K_1") (pintype "passive"))
      (node (ref "LED208") (pin "1") (pinfunction "K_1") (pintype "passive"))
      (node (ref "X2") (pin "13") (pinfunction "13_13") (pintype "passive"))
    )
    (net (code "30") (name "Net-(LED209-K)") (class "Default")
      (node (ref "LED209") (pin "1") (pinfunction "K_1") (pintype "passive"))
      (node (ref "LED210") (pin "1") (pinfunction "K_1") (pintype "passive"))
      (node (ref "LED211") (pin "1") (pinfunction "K_1") (pintype "passive"))
      (node (ref "LED212") (pin "1") (pinfunction "K_1") (pintype "passive"))
      (node (ref "LED213") (pin "1") (pinfunction "K_1") (pintype "passive"))
      (node (ref "LED214") (pin "1") (pinfunction "K_1") (pintype "passive"))
      (node (ref "LED215") (pin "1") (pinfunction "K_1") (pintype "passive"))
      (node (ref "LED216") (pin "1") (pinfunction "K_1") (pintype "passive"))
      (node (ref "LED217") (pin "1") (pinfunction "K_1") (pintype "passive"))
      (node (ref "LED218") (pin "1") (pinfunction "K_1") (pintype "passive"))
      (node (ref "LED219") (pin "1") (pinfunction "K_1") (pintype "passive"))
      (node (ref "LED220") (pin "1") (pinfunction "K_1") (pintype "passive"))
      (node (ref "LED221") (pin "1") (pinfunction "K_1") (pintype "passive"))
      (node (ref "LED222") (pin "1") (pinfunction "K_1") (pintype "passive"))
      (node (ref "LED223") (pin "1") (pinfunction "K_1") (pintype "passive"))
      (node (ref "LED224") (pin "1") (pinfunction "K_1") (pintype "passive"))
      (node (ref "X2") (pin "14") (pinfunction "14_14") (pintype "passive"))
    )
    (net (code "31") (name "Net-(LED225-K)") (class "Default")
      (node (ref "LED225") (pin "1") (pinfunction "K_1") (pintype "passive"))
      (node (ref "LED226") (pin "1") (pinfunction "K_1") (pintype "passive"))
      (node (ref "LED227") (pin "1") (pinfunction "K_1") (pintype "passive"))
      (node (ref "LED228") (pin "1") (pinfunction "K_1") (pintype "passive"))
      (node (ref "LED229") (pin "1") (pinfunction "K_1") (pintype "passive"))
      (node (ref "LED230") (pin "1") (pinfunction "K_1") (pintype "passive"))
      (node (ref "LED231") (pin "1") (pinfunction "K_1") (pintype "passive"))
      (node (ref "LED232") (pin "1") (pinfunction "K_1") (pintype "passive"))
      (node (ref "LED233") (pin "1") (pinfunction "K_1") (pintype "passive"))
      (node (ref "LED234") (pin "1") (pinfunction "K_1") (pintype "passive"))
      (node (ref "LED235") (pin "1") (pinfunction "K_1") (pintype "passive"))
      (node (ref "LED236") (pin "1") (pinfunction "K_1") (pintype "passive"))
      (node (ref "LED237") (pin "1") (pinfunction "K_1") (pintype "passive"))
      (node (ref "LED238") (pin "1") (pinfunction "K_1") (pintype "passive"))
      (node (ref "LED239") (pin "1") (pinfunction "K_1") (pintype "passive"))
      (node (ref "LED240") (pin "1") (pinfunction "K_1") (pintype "passive"))
      (node (ref "X2") (pin "15") (pinfunction "15_15") (pintype "passive"))
    )
    (net (code "32") (name "Net-(LED241-K)") (class "Default")
      (node (ref "LED241") (pin "1") (pinfunction "K_1") (pintype "passive"))
      (node (ref "LED242") (pin "1") (pinfunction "K_1") (pintype "passive"))
      (node (ref "LED243") (pin "1") (pinfunction "K_1") (pintype "passive"))
      (node (ref "LED244") (pin "1") (pinfunction "K_1") (pintype "passive"))
      (node (ref "LED245") (pin "1") (pinfunction "K_1") (pintype "passive"))
      (node (ref "LED246") (pin "1") (pinfunction "K_1") (pintype "passive"))
      (node (ref "LED247") (pin "1") (pinfunction "K_1") (pintype "passive"))
      (node (ref "LED248") (pin "1") (pinfunction "K_1") (pintype "passive"))
      (node (ref "LED249") (pin "1") (pinfunction "K_1") (pintype "passive"))
      (node (ref "LED250") (pin "1") (pinfunction "K_1") (pintype "passive"))
      (node (ref "LED251") (pin "1") (pinfunction "K_1") (pintype "passive"))
      (node (ref "LED252") (pin "1") (pinfunction "K_1") (pintype "passive"))
      (node (ref "LED253") (pin "1") (pinfunction "K_1") (pintype "passive"))
      (node (ref "LED254") (pin "1") (pinfunction "K_1") (pintype "passive"))
      (node (ref "LED255") (pin "1") (pinfunction "K_1") (pintype "passive"))
      (node (ref "LED256") (pin "1") (pinfunction "K_1") (pintype "passive"))
      (node (ref "X2") (pin "16") (pinfunction "16_16") (pintype "passive"))
    )
  )
)
